# SCH_A320_MCDU_SMD_2023-03-02.net
KiCad netlist of a schematic drawn in EasyEDA
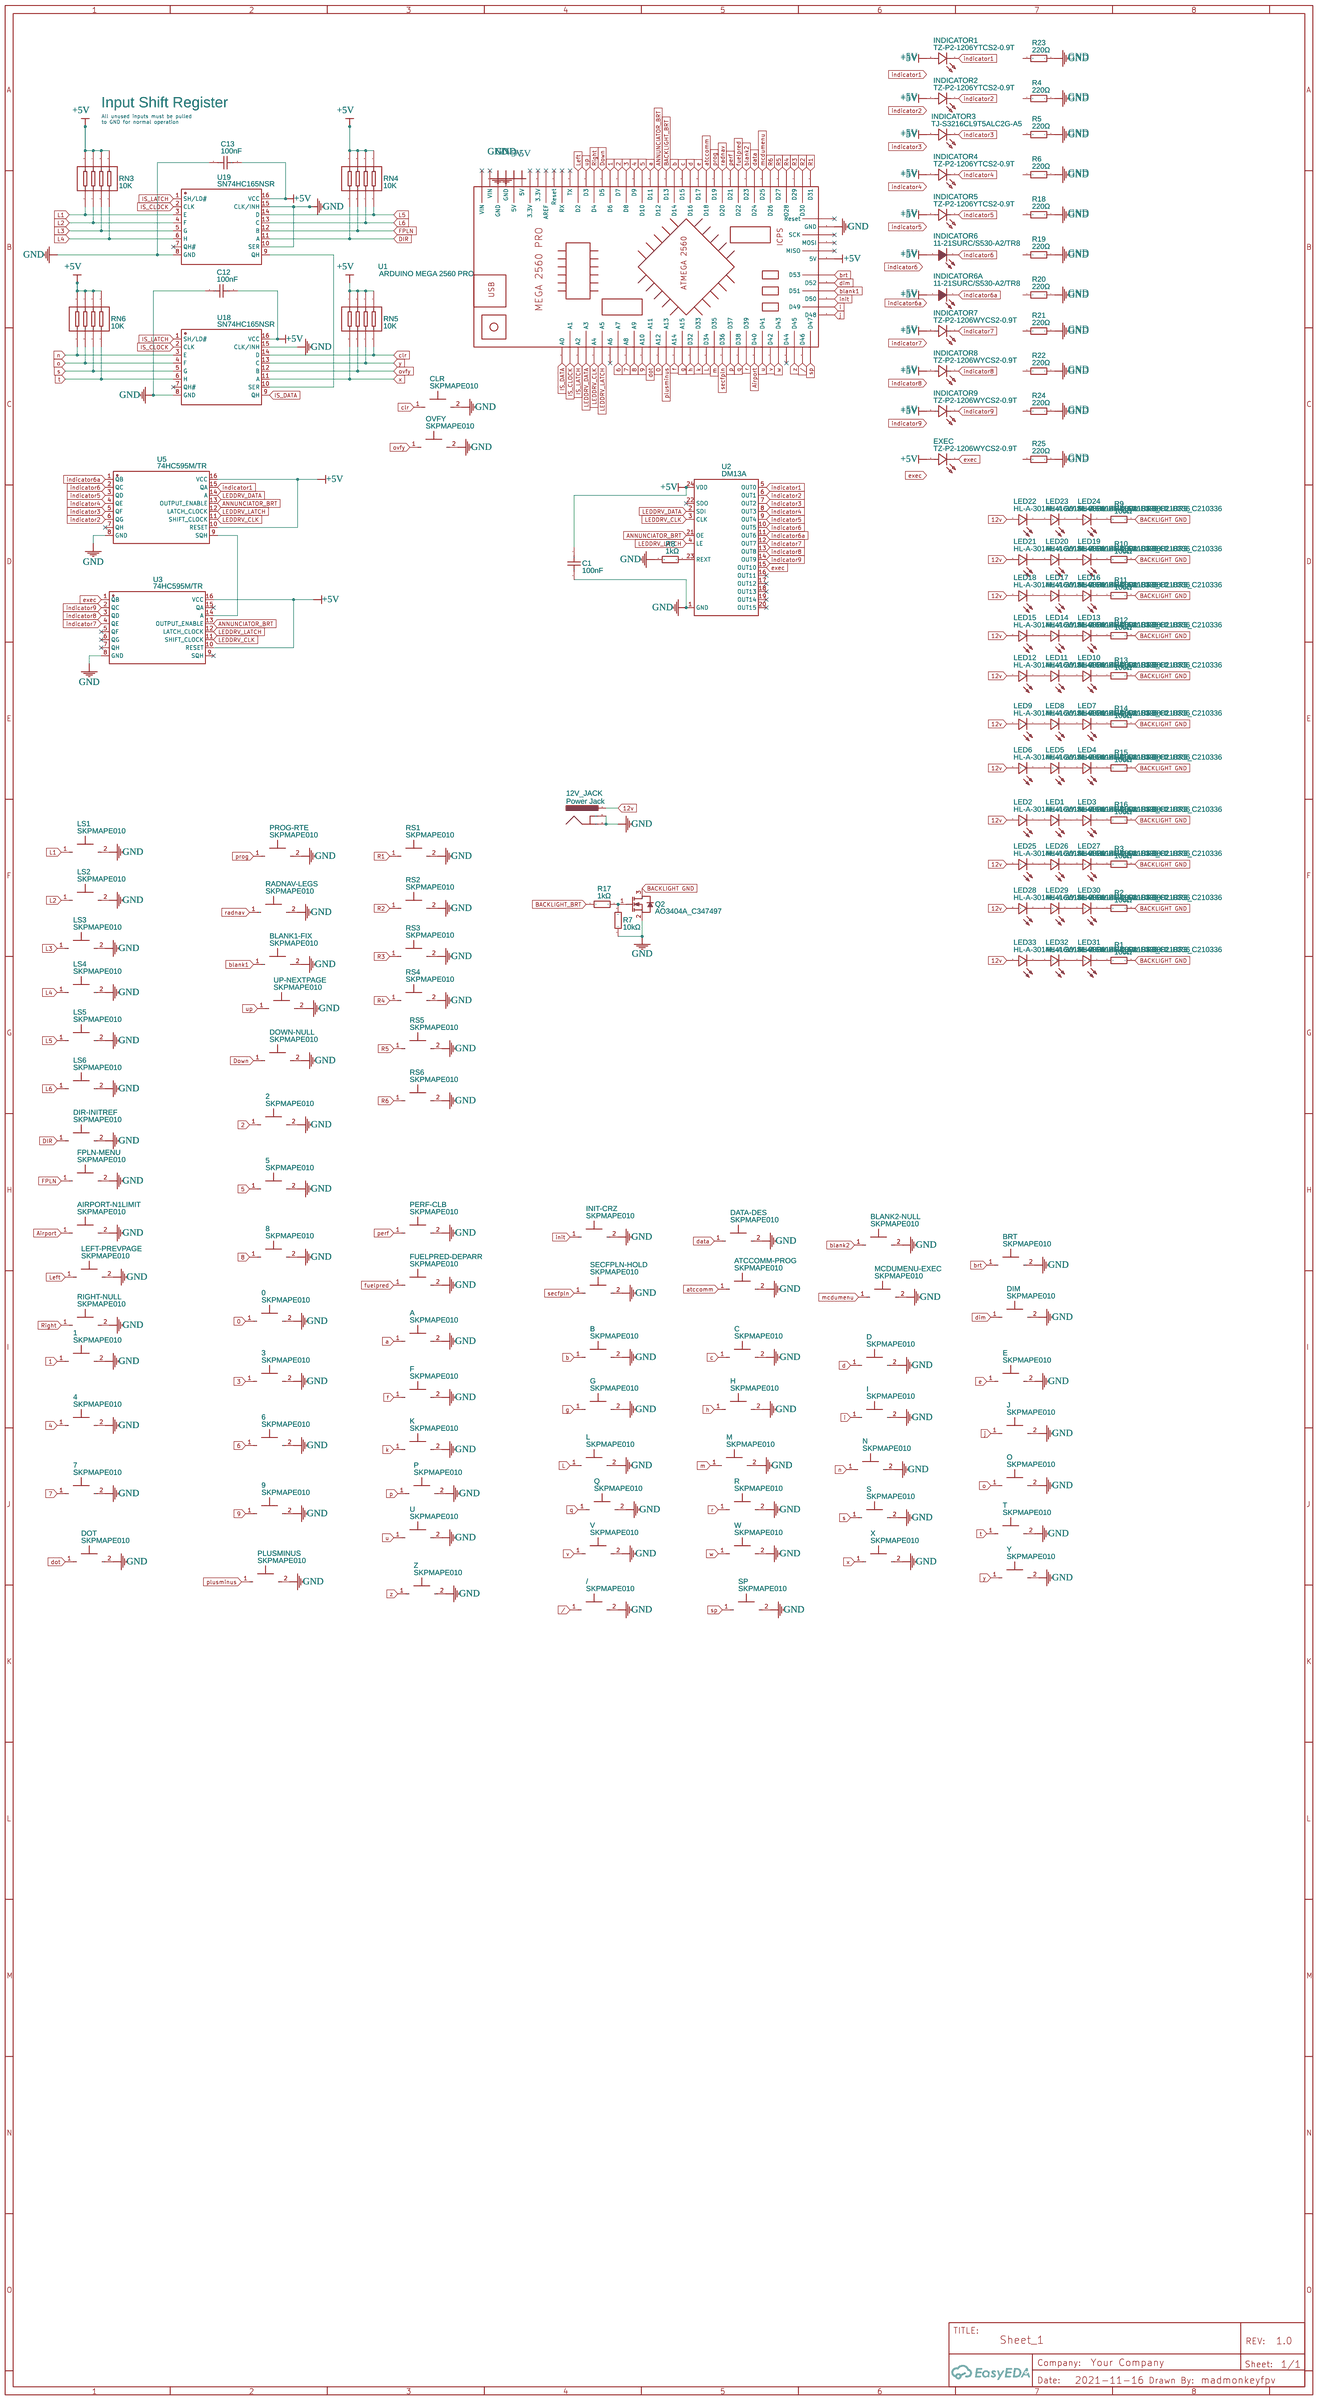
[diagram p0: schematic sheet]

(export (version "E")
  (design (tool "Eeschema 10.0.6"))
  (components
    (comp (ref "/")
      (value "SKPMAPE010")
      (fields (field (name "BOM_Supplier Part") "C110292"))
      (libsource (lib "") (part "SKPMAPE010_19"))
    )
    (comp (ref "0")
      (value "SKPMAPE010")
      (fields (field (name "BOM_Supplier Part") "C110292"))
      (libsource (lib "") (part "SKPMAPE010_6"))
    )
    (comp (ref "1")
      (value "SKPMAPE010")
      (fields (field (name "BOM_Supplier Part") "C110292"))
      (libsource (lib "") (part "SKPMAPE010_6"))
    )
    (comp (ref "2")
      (value "SKPMAPE010")
      (fields (field (name "BOM_Supplier Part") "C110292"))
      (libsource (lib "") (part "SKPMAPE010_6"))
    )
    (comp (ref "3")
      (value "SKPMAPE010")
      (fields (field (name "BOM_Supplier Part") "C110292"))
      (libsource (lib "") (part "SKPMAPE010_6"))
    )
    (comp (ref "4")
      (value "SKPMAPE010")
      (fields (field (name "BOM_Supplier Part") "C110292"))
      (libsource (lib "") (part "SKPMAPE010_6"))
    )
    (comp (ref "5")
      (value "SKPMAPE010")
      (fields (field (name "BOM_Supplier Part") "C110292"))
      (libsource (lib "") (part "SKPMAPE010_6"))
    )
    (comp (ref "6")
      (value "SKPMAPE010")
      (fields (field (name "BOM_Supplier Part") "C110292"))
      (libsource (lib "") (part "SKPMAPE010_6"))
    )
    (comp (ref "7")
      (value "SKPMAPE010")
      (fields (field (name "BOM_Supplier Part") "C110292"))
      (libsource (lib "") (part "SKPMAPE010_6"))
    )
    (comp (ref "8")
      (value "SKPMAPE010")
      (fields (field (name "BOM_Supplier Part") "C110292"))
      (libsource (lib "") (part "SKPMAPE010_6"))
    )
    (comp (ref "9")
      (value "SKPMAPE010")
      (fields (field (name "BOM_Supplier Part") "C110292"))
      (libsource (lib "") (part "SKPMAPE010_6"))
    )
    (comp (ref "12V_JACK")
      (value "Power Jack")
      (fields (field (name "BOM_Supplier Part") "A-4118"))
      (libsource (lib "") (part "POWER_JACK"))
    )
    (comp (ref "A")
      (value "SKPMAPE010")
      (fields (field (name "BOM_Supplier Part") "C110292"))
      (libsource (lib "") (part "SKPMAPE010_34"))
    )
    (comp (ref "AIRPORT-N1LIMIT")
      (value "SKPMAPE010")
      (fields (field (name "BOM_Supplier Part") "C110292"))
      (libsource (lib "") (part "SKPMAPE010_46"))
    )
    (comp (ref "ATCCOMM-PROG")
      (value "SKPMAPE010")
      (fields (field (name "BOM_Supplier Part") "C110292"))
      (libsource (lib "") (part "SKPMAPE010_37"))
    )
    (comp (ref "B")
      (value "SKPMAPE010")
      (fields (field (name "BOM_Supplier Part") "C110292"))
      (libsource (lib "") (part "SKPMAPE010_43"))
    )
    (comp (ref "BLANK1-FIX")
      (value "SKPMAPE010")
      (fields (field (name "BOM_Supplier Part") "C110292"))
      (libsource (lib "") (part "SKPMAPE010_17"))
    )
    (comp (ref "BLANK2-NULL")
      (value "SKPMAPE010")
      (fields (field (name "BOM_Supplier Part") "C110292"))
      (libsource (lib "") (part "SKPMAPE010_31"))
    )
    (comp (ref "BRT")
      (value "SKPMAPE010")
      (fields (field (name "BOM_Supplier Part") "C110292"))
      (libsource (lib "") (part "SKPMAPE010_32"))
    )
    (comp (ref "C")
      (value "SKPMAPE010")
      (fields (field (name "BOM_Supplier Part") "C110292"))
      (libsource (lib "") (part "SKPMAPE010_50"))
    )
    (comp (ref "C1")
      (value "100nF")
      (fields
        (field (name "BOM_Manufacturer Part") "CC0603KRX7R9BB104")
        (field (name "BOM_Supplier Part") "C14663")
      )
      (libsource (lib "") (part "CC0603KRX7R9BB104_1"))
    )
    (comp (ref "C12")
      (value "100nF")
      (fields
        (field (name "BOM_Manufacturer Part") "CC0603KRX7R9BB104")
        (field (name "BOM_Supplier Part") "C14663")
      )
      (libsource (lib "") (part "CC0603KRX7R9BB104"))
    )
    (comp (ref "C13")
      (value "100nF")
      (fields
        (field (name "BOM_Manufacturer Part") "CC0603KRX7R9BB104")
        (field (name "BOM_Supplier Part") "C14663")
      )
      (libsource (lib "") (part "CC0603KRX7R9BB104"))
    )
    (comp (ref "CLR")
      (value "SKPMAPE010")
      (fields (field (name "BOM_Supplier Part") "C110292"))
      (libsource (lib "") (part "SKPMAPE010_7"))
    )
    (comp (ref "D")
      (value "SKPMAPE010")
      (fields (field (name "BOM_Supplier Part") "C110292"))
      (libsource (lib "") (part "SKPMAPE010_54"))
    )
    (comp (ref "DATA-DES")
      (value "SKPMAPE010")
      (fields (field (name "BOM_Supplier Part") "C110292"))
      (libsource (lib "") (part "SKPMAPE010_28"))
    )
    (comp (ref "DIM")
      (value "SKPMAPE010")
      (fields (field (name "BOM_Supplier Part") "C110292"))
      (libsource (lib "") (part "SKPMAPE010_26"))
    )
    (comp (ref "DIR-INITREF")
      (value "SKPMAPE010")
      (fields (field (name "BOM_Supplier Part") "C110292"))
      (libsource (lib "") (part "SKPMAPE010_2"))
    )
    (comp (ref "DOT")
      (value "SKPMAPE010")
      (fields (field (name "BOM_Supplier Part") "C110292"))
      (libsource (lib "") (part "SKPMAPE010_20"))
    )
    (comp (ref "DOWN-NULL")
      (value "SKPMAPE010")
      (fields (field (name "BOM_Supplier Part") "C110292"))
      (libsource (lib "") (part "SKPMAPE010_33"))
    )
    (comp (ref "E")
      (value "SKPMAPE010")
      (fields (field (name "BOM_Supplier Part") "C110292"))
      (libsource (lib "") (part "SKPMAPE010_52"))
    )
    (comp (ref "EXEC")
      (value "TZ-P2-1206WYCS2-0.9T")
      (fields (field (name "BOM_Supplier Part") "C779809"))
      (libsource (lib "") (part "TZ-P2-1206WYCS2-0.9T_1"))
    )
    (comp (ref "F")
      (value "SKPMAPE010")
      (fields (field (name "BOM_Supplier Part") "C110292"))
      (libsource (lib "") (part "SKPMAPE010_45"))
    )
    (comp (ref "FPLN-MENU")
      (value "SKPMAPE010")
      (fields (field (name "BOM_Supplier Part") "C110292"))
      (libsource (lib "") (part "SKPMAPE010_48"))
    )
    (comp (ref "FUELPRED-DEPARR")
      (value "SKPMAPE010")
      (fields (field (name "BOM_Supplier Part") "C110292"))
      (libsource (lib "") (part "SKPMAPE010_18"))
    )
    (comp (ref "G")
      (value "SKPMAPE010")
      (fields (field (name "BOM_Supplier Part") "C110292"))
      (libsource (lib "") (part "SKPMAPE010_27"))
    )
    (comp (ref "H")
      (value "SKPMAPE010")
      (fields (field (name "BOM_Supplier Part") "C110292"))
      (libsource (lib "") (part "SKPMAPE010_5"))
    )
    (comp (ref "I")
      (value "SKPMAPE010")
      (fields (field (name "BOM_Supplier Part") "C110292"))
      (libsource (lib "") (part "SKPMAPE010_53"))
    )
    (comp (ref "INDICATOR1")
      (value "TZ-P2-1206YTCS2-0.9T")
      (fields (field (name "BOM_Supplier Part") "C779811"))
      (libsource (lib "") (part "TZ-P2-1206YTCS2-0.9T"))
    )
    (comp (ref "INDICATOR2")
      (value "TZ-P2-1206YTCS2-0.9T")
      (fields (field (name "BOM_Supplier Part") "C779811"))
      (libsource (lib "") (part "TZ-P2-1206YTCS2-0.9T"))
    )
    (comp (ref "INDICATOR3")
      (value "TJ-S3216CL9T5ALC2G-A5")
      (fields (field (name "BOM_Supplier Part") "C917196"))
      (libsource (lib "") (part "TJ-S3216CL9T5ALC2G-A5"))
    )
    (comp (ref "INDICATOR4")
      (value "TZ-P2-1206YTCS2-0.9T")
      (fields (field (name "BOM_Supplier Part") "C779811"))
      (libsource (lib "") (part "TZ-P2-1206YTCS2-0.9T"))
    )
    (comp (ref "INDICATOR5")
      (value "TZ-P2-1206YTCS2-0.9T")
      (fields (field (name "BOM_Supplier Part") "C779811"))
      (libsource (lib "") (part "TZ-P2-1206YTCS2-0.9T"))
    )
    (comp (ref "INDICATOR6")
      (value "11-21SURC/S530-A2/TR8")
      (fields (field (name "BOM_Supplier Part") "C264315"))
      (libsource (lib "") (part "11-21SURC/S530-A2/TR8"))
    )
    (comp (ref "INDICATOR6A")
      (value "11-21SURC/S530-A2/TR8")
      (fields (field (name "BOM_Supplier Part") "C264315"))
      (libsource (lib "") (part "11-21SURC/S530-A2/TR8_1"))
    )
    (comp (ref "INDICATOR7")
      (value "TZ-P2-1206WYCS2-0.9T")
      (fields (field (name "BOM_Supplier Part") "C779809"))
      (libsource (lib "") (part "TZ-P2-1206WYCS2-0.9T"))
    )
    (comp (ref "INDICATOR8")
      (value "TZ-P2-1206WYCS2-0.9T")
      (fields (field (name "BOM_Supplier Part") "C779809"))
      (libsource (lib "") (part "TZ-P2-1206WYCS2-0.9T"))
    )
    (comp (ref "INDICATOR9")
      (value "TZ-P2-1206WYCS2-0.9T")
      (fields (field (name "BOM_Supplier Part") "C779809"))
      (libsource (lib "") (part "TZ-P2-1206WYCS2-0.9T"))
    )
    (comp (ref "INIT-CRZ")
      (value "SKPMAPE010")
      (fields (field (name "BOM_Supplier Part") "C110292"))
      (libsource (lib "") (part "SKPMAPE010"))
    )
    (comp (ref "J")
      (value "SKPMAPE010")
      (fields (field (name "BOM_Supplier Part") "C110292"))
      (libsource (lib "") (part "SKPMAPE010_3"))
    )
    (comp (ref "K")
      (value "SKPMAPE010")
      (fields (field (name "BOM_Supplier Part") "C110292"))
      (libsource (lib "") (part "SKPMAPE010_9"))
    )
    (comp (ref "L")
      (value "SKPMAPE010")
      (fields (field (name "BOM_Supplier Part") "C110292"))
      (libsource (lib "") (part "SKPMAPE010_8"))
    )
    (comp (ref "LED1")
      (value "HL-A-3014H416W-S1-08HL-HR3_C210336")
      (fields (field (name "BOM_Supplier Part") "C210336"))
      (libsource (lib "") (part "HL-A-3014H416W-S1-08HL-HR3_C210336"))
    )
    (comp (ref "LED2")
      (value "HL-A-3014H416W-S1-08HL-HR3_C210336")
      (fields (field (name "BOM_Supplier Part") "C210336"))
      (libsource (lib "") (part "HL-A-3014H416W-S1-08HL-HR3_C210336"))
    )
    (comp (ref "LED3")
      (value "HL-A-3014H416W-S1-08HL-HR3_C210336")
      (fields (field (name "BOM_Supplier Part") "C210336"))
      (libsource (lib "") (part "HL-A-3014H416W-S1-08HL-HR3_C210336"))
    )
    (comp (ref "LED4")
      (value "HL-A-3014H416W-S1-08HL-HR3_C210336")
      (fields (field (name "BOM_Supplier Part") "C210336"))
      (libsource (lib "") (part "HL-A-3014H416W-S1-08HL-HR3_C210336"))
    )
    (comp (ref "LED5")
      (value "HL-A-3014H416W-S1-08HL-HR3_C210336")
      (fields (field (name "BOM_Supplier Part") "C210336"))
      (libsource (lib "") (part "HL-A-3014H416W-S1-08HL-HR3_C210336"))
    )
    (comp (ref "LED6")
      (value "HL-A-3014H416W-S1-08HL-HR3_C210336")
      (fields (field (name "BOM_Supplier Part") "C210336"))
      (libsource (lib "") (part "HL-A-3014H416W-S1-08HL-HR3_C210336"))
    )
    (comp (ref "LED7")
      (value "HL-A-3014H416W-S1-08HL-HR3_C210336")
      (fields (field (name "BOM_Supplier Part") "C210336"))
      (libsource (lib "") (part "HL-A-3014H416W-S1-08HL-HR3_C210336"))
    )
    (comp (ref "LED8")
      (value "HL-A-3014H416W-S1-08HL-HR3_C210336")
      (fields (field (name "BOM_Supplier Part") "C210336"))
      (libsource (lib "") (part "HL-A-3014H416W-S1-08HL-HR3_C210336"))
    )
    (comp (ref "LED9")
      (value "HL-A-3014H416W-S1-08HL-HR3_C210336")
      (fields (field (name "BOM_Supplier Part") "C210336"))
      (libsource (lib "") (part "HL-A-3014H416W-S1-08HL-HR3_C210336"))
    )
    (comp (ref "LED10")
      (value "HL-A-3014H416W-S1-08HL-HR3_C210336")
      (fields (field (name "BOM_Supplier Part") "C210336"))
      (libsource (lib "") (part "HL-A-3014H416W-S1-08HL-HR3_C210336"))
    )
    (comp (ref "LED11")
      (value "HL-A-3014H416W-S1-08HL-HR3_C210336")
      (fields (field (name "BOM_Supplier Part") "C210336"))
      (libsource (lib "") (part "HL-A-3014H416W-S1-08HL-HR3_C210336"))
    )
    (comp (ref "LED12")
      (value "HL-A-3014H416W-S1-08HL-HR3_C210336")
      (fields (field (name "BOM_Supplier Part") "C210336"))
      (libsource (lib "") (part "HL-A-3014H416W-S1-08HL-HR3_C210336"))
    )
    (comp (ref "LED13")
      (value "HL-A-3014H416W-S1-08HL-HR3_C210336")
      (fields (field (name "BOM_Supplier Part") "C210336"))
      (libsource (lib "") (part "HL-A-3014H416W-S1-08HL-HR3_C210336"))
    )
    (comp (ref "LED14")
      (value "HL-A-3014H416W-S1-08HL-HR3_C210336")
      (fields (field (name "BOM_Supplier Part") "C210336"))
      (libsource (lib "") (part "HL-A-3014H416W-S1-08HL-HR3_C210336"))
    )
    (comp (ref "LED15")
      (value "HL-A-3014H416W-S1-08HL-HR3_C210336")
      (fields (field (name "BOM_Supplier Part") "C210336"))
      (libsource (lib "") (part "HL-A-3014H416W-S1-08HL-HR3_C210336"))
    )
    (comp (ref "LED16")
      (value "HL-A-3014H416W-S1-08HL-HR3_C210336")
      (fields (field (name "BOM_Supplier Part") "C210336"))
      (libsource (lib "") (part "HL-A-3014H416W-S1-08HL-HR3_C210336"))
    )
    (comp (ref "LED17")
      (value "HL-A-3014H416W-S1-08HL-HR3_C210336")
      (fields (field (name "BOM_Supplier Part") "C210336"))
      (libsource (lib "") (part "HL-A-3014H416W-S1-08HL-HR3_C210336"))
    )
    (comp (ref "LED18")
      (value "HL-A-3014H416W-S1-08HL-HR3_C210336")
      (fields (field (name "BOM_Supplier Part") "C210336"))
      (libsource (lib "") (part "HL-A-3014H416W-S1-08HL-HR3_C210336"))
    )
    (comp (ref "LED19")
      (value "HL-A-3014H416W-S1-08HL-HR3_C210336")
      (fields (field (name "BOM_Supplier Part") "C210336"))
      (libsource (lib "") (part "HL-A-3014H416W-S1-08HL-HR3_C210336"))
    )
    (comp (ref "LED20")
      (value "HL-A-3014H416W-S1-08HL-HR3_C210336")
      (fields (field (name "BOM_Supplier Part") "C210336"))
      (libsource (lib "") (part "HL-A-3014H416W-S1-08HL-HR3_C210336"))
    )
    (comp (ref "LED21")
      (value "HL-A-3014H416W-S1-08HL-HR3_C210336")
      (fields (field (name "BOM_Supplier Part") "C210336"))
      (libsource (lib "") (part "HL-A-3014H416W-S1-08HL-HR3_C210336"))
    )
    (comp (ref "LED22")
      (value "HL-A-3014H416W-S1-08HL-HR3_C210336")
      (fields (field (name "BOM_Supplier Part") "C210336"))
      (libsource (lib "") (part "HL-A-3014H416W-S1-08HL-HR3_C210336"))
    )
    (comp (ref "LED23")
      (value "HL-A-3014H416W-S1-08HL-HR3_C210336")
      (fields (field (name "BOM_Supplier Part") "C210336"))
      (libsource (lib "") (part "HL-A-3014H416W-S1-08HL-HR3_C210336"))
    )
    (comp (ref "LED24")
      (value "HL-A-3014H416W-S1-08HL-HR3_C210336")
      (fields (field (name "BOM_Supplier Part") "C210336"))
      (libsource (lib "") (part "HL-A-3014H416W-S1-08HL-HR3_C210336"))
    )
    (comp (ref "LED25")
      (value "HL-A-3014H416W-S1-08HL-HR3_C210336")
      (fields (field (name "BOM_Supplier Part") "C210336"))
      (libsource (lib "") (part "HL-A-3014H416W-S1-08HL-HR3_C210336"))
    )
    (comp (ref "LED26")
      (value "HL-A-3014H416W-S1-08HL-HR3_C210336")
      (fields (field (name "BOM_Supplier Part") "C210336"))
      (libsource (lib "") (part "HL-A-3014H416W-S1-08HL-HR3_C210336"))
    )
    (comp (ref "LED27")
      (value "HL-A-3014H416W-S1-08HL-HR3_C210336")
      (fields (field (name "BOM_Supplier Part") "C210336"))
      (libsource (lib "") (part "HL-A-3014H416W-S1-08HL-HR3_C210336"))
    )
    (comp (ref "LED28")
      (value "HL-A-3014H416W-S1-08HL-HR3_C210336")
      (fields (field (name "BOM_Supplier Part") "C210336"))
      (libsource (lib "") (part "HL-A-3014H416W-S1-08HL-HR3_C210336"))
    )
    (comp (ref "LED29")
      (value "HL-A-3014H416W-S1-08HL-HR3_C210336")
      (fields (field (name "BOM_Supplier Part") "C210336"))
      (libsource (lib "") (part "HL-A-3014H416W-S1-08HL-HR3_C210336"))
    )
    (comp (ref "LED30")
      (value "HL-A-3014H416W-S1-08HL-HR3_C210336")
      (fields (field (name "BOM_Supplier Part") "C210336"))
      (libsource (lib "") (part "HL-A-3014H416W-S1-08HL-HR3_C210336"))
    )
    (comp (ref "LED31")
      (value "HL-A-3014H416W-S1-08HL-HR3_C210336")
      (fields (field (name "BOM_Supplier Part") "C210336"))
      (libsource (lib "") (part "HL-A-3014H416W-S1-08HL-HR3_C210336"))
    )
    (comp (ref "LED32")
      (value "HL-A-3014H416W-S1-08HL-HR3_C210336")
      (fields (field (name "BOM_Supplier Part") "C210336"))
      (libsource (lib "") (part "HL-A-3014H416W-S1-08HL-HR3_C210336"))
    )
    (comp (ref "LED33")
      (value "HL-A-3014H416W-S1-08HL-HR3_C210336")
      (fields (field (name "BOM_Supplier Part") "C210336"))
      (libsource (lib "") (part "HL-A-3014H416W-S1-08HL-HR3_C210336"))
    )
    (comp (ref "LEFT-PREVPAGE")
      (value "SKPMAPE010")
      (fields (field (name "BOM_Supplier Part") "C110292"))
      (libsource (lib "") (part "SKPMAPE010_14"))
    )
    (comp (ref "LS1")
      (value "SKPMAPE010")
      (fields (field (name "BOM_Supplier Part") "C110292"))
      (libsource (lib "") (part "SKPMAPE010_12"))
    )
    (comp (ref "LS2")
      (value "SKPMAPE010")
      (fields (field (name "BOM_Supplier Part") "C110292"))
      (libsource (lib "") (part "SKPMAPE010_12"))
    )
    (comp (ref "LS3")
      (value "SKPMAPE010")
      (fields (field (name "BOM_Supplier Part") "C110292"))
      (libsource (lib "") (part "SKPMAPE010_12"))
    )
    (comp (ref "LS4")
      (value "SKPMAPE010")
      (fields (field (name "BOM_Supplier Part") "C110292"))
      (libsource (lib "") (part "SKPMAPE010_12"))
    )
    (comp (ref "LS5")
      (value "SKPMAPE010")
      (fields (field (name "BOM_Supplier Part") "C110292"))
      (libsource (lib "") (part "SKPMAPE010_12"))
    )
    (comp (ref "LS6")
      (value "SKPMAPE010")
      (fields (field (name "BOM_Supplier Part") "C110292"))
      (libsource (lib "") (part "SKPMAPE010_12"))
    )
    (comp (ref "M")
      (value "SKPMAPE010")
      (fields (field (name "BOM_Supplier Part") "C110292"))
      (libsource (lib "") (part "SKPMAPE010_41"))
    )
    (comp (ref "MCDUMENU-EXEC")
      (value "SKPMAPE010")
      (fields (field (name "BOM_Supplier Part") "C110292"))
      (libsource (lib "") (part "SKPMAPE010_24"))
    )
    (comp (ref "N")
      (value "SKPMAPE010")
      (fields (field (name "BOM_Supplier Part") "C110292"))
      (libsource (lib "") (part "SKPMAPE010_49"))
    )
    (comp (ref "O")
      (value "SKPMAPE010")
      (fields (field (name "BOM_Supplier Part") "C110292"))
      (libsource (lib "") (part "SKPMAPE010_1"))
    )
    (comp (ref "OVFY")
      (value "SKPMAPE010")
      (fields (field (name "BOM_Supplier Part") "C110292"))
      (libsource (lib "") (part "SKPMAPE010_4"))
    )
    (comp (ref "P")
      (value "SKPMAPE010")
      (fields (field (name "BOM_Supplier Part") "C110292"))
      (libsource (lib "") (part "SKPMAPE010_35"))
    )
    (comp (ref "PERF-CLB")
      (value "SKPMAPE010")
      (fields (field (name "BOM_Supplier Part") "C110292"))
      (libsource (lib "") (part "SKPMAPE010_44"))
    )
    (comp (ref "PLUSMINUS")
      (value "SKPMAPE010")
      (fields (field (name "BOM_Supplier Part") "C110292"))
      (libsource (lib "") (part "SKPMAPE010_21"))
    )
    (comp (ref "PROG-RTE")
      (value "SKPMAPE010")
      (fields (field (name "BOM_Supplier Part") "C110292"))
      (libsource (lib "") (part "SKPMAPE010_11"))
    )
    (comp (ref "Q")
      (value "SKPMAPE010")
      (fields (field (name "BOM_Supplier Part") "C110292"))
      (libsource (lib "") (part "SKPMAPE010_30"))
    )
    (comp (ref "Q2")
      (value "AO3404A_C347497")
      (fields (field (name "BOM_Manufacturer Part") "AO3404A") (field (name "BOM_Supplier Part") "C347497"))
      (libsource (lib "") (part "AO3404A_C347497"))
    )
    (comp (ref "R")
      (value "SKPMAPE010")
      (fields (field (name "BOM_Supplier Part") "C110292"))
      (libsource (lib "") (part "SKPMAPE010_29"))
    )
    (comp (ref "R1")
      (value "100Ω")
      (fields
        (field (name "BOM_Manufacturer Part") "1206W4F1000T5E")
        (field (name "BOM_Supplier Part") "C17901")
      )
      (libsource (lib "") (part "1206W4F1000T5E"))
    )
    (comp (ref "R2")
      (value "100Ω")
      (fields
        (field (name "BOM_Manufacturer Part") "1206W4F1000T5E")
        (field (name "BOM_Supplier Part") "C17901")
      )
      (libsource (lib "") (part "1206W4F1000T5E"))
    )
    (comp (ref "R3")
      (value "100Ω")
      (fields
        (field (name "BOM_Manufacturer Part") "1206W4F1000T5E")
        (field (name "BOM_Supplier Part") "C17901")
      )
      (libsource (lib "") (part "1206W4F1000T5E"))
    )
    (comp (ref "R4")
      (value "220Ω")
      (fields
        (field (name "BOM_Manufacturer Part") "0805W8F2200T5E")
        (field (name "BOM_Supplier Part") "C17557")
      )
      (libsource (lib "") (part "0805W8F2200T5E"))
    )
    (comp (ref "R5")
      (value "220Ω")
      (fields
        (field (name "BOM_Manufacturer Part") "0805W8F2200T5E")
        (field (name "BOM_Supplier Part") "C17557")
      )
      (libsource (lib "") (part "0805W8F2200T5E"))
    )
    (comp (ref "R6")
      (value "220Ω")
      (fields
        (field (name "BOM_Manufacturer Part") "0805W8F2200T5E")
        (field (name "BOM_Supplier Part") "C17557")
      )
      (libsource (lib "") (part "0805W8F2200T5E"))
    )
    (comp (ref "R7")
      (value "10kΩ")
      (fields
        (field (name "BOM_Manufacturer Part") "1206W4F1002T5E")
        (field (name "BOM_Supplier Part") "C17902")
      )
      (libsource (lib "") (part "1206W4F1002T5E"))
    )
    (comp (ref "R8")
      (value "1kΩ")
      (fields
        (field (name "BOM_Manufacturer Part") "1206W4F1001T5E")
        (field (name "BOM_Supplier Part") "C4410")
      )
      (libsource (lib "") (part "1206W4F1001T5E_1"))
    )
    (comp (ref "R9")
      (value "100Ω")
      (fields
        (field (name "BOM_Manufacturer Part") "1206W4F1000T5E")
        (field (name "BOM_Supplier Part") "C17901")
      )
      (libsource (lib "") (part "1206W4F1000T5E"))
    )
    (comp (ref "R10")
      (value "100Ω")
      (fields
        (field (name "BOM_Manufacturer Part") "1206W4F1000T5E")
        (field (name "BOM_Supplier Part") "C17901")
      )
      (libsource (lib "") (part "1206W4F1000T5E"))
    )
    (comp (ref "R11")
      (value "100Ω")
      (fields
        (field (name "BOM_Manufacturer Part") "1206W4F1000T5E")
        (field (name "BOM_Supplier Part") "C17901")
      )
      (libsource (lib "") (part "1206W4F1000T5E"))
    )
    (comp (ref "R12")
      (value "100Ω")
      (fields
        (field (name "BOM_Manufacturer Part") "1206W4F1000T5E")
        (field (name "BOM_Supplier Part") "C17901")
      )
      (libsource (lib "") (part "1206W4F1000T5E"))
    )
    (comp (ref "R13")
      (value "100Ω")
      (fields
        (field (name "BOM_Manufacturer Part") "1206W4F1000T5E")
        (field (name "BOM_Supplier Part") "C17901")
      )
      (libsource (lib "") (part "1206W4F1000T5E"))
    )
    (comp (ref "R14")
      (value "100Ω")
      (fields
        (field (name "BOM_Manufacturer Part") "1206W4F1000T5E")
        (field (name "BOM_Supplier Part") "C17901")
      )
      (libsource (lib "") (part "1206W4F1000T5E"))
    )
    (comp (ref "R15")
      (value "100Ω")
      (fields
        (field (name "BOM_Manufacturer Part") "1206W4F1000T5E")
        (field (name "BOM_Supplier Part") "C17901")
      )
      (libsource (lib "") (part "1206W4F1000T5E"))
    )
    (comp (ref "R16")
      (value "100Ω")
      (fields
        (field (name "BOM_Manufacturer Part") "1206W4F1000T5E")
        (field (name "BOM_Supplier Part") "C17901")
      )
      (libsource (lib "") (part "1206W4F1000T5E"))
    )
    (comp (ref "R17")
      (value "1kΩ")
      (fields
        (field (name "BOM_Manufacturer Part") "1206W4F1001T5E")
        (field (name "BOM_Supplier Part") "C4410")
      )
      (libsource (lib "") (part "1206W4F1001T5E"))
    )
    (comp (ref "R18")
      (value "220Ω")
      (fields
        (field (name "BOM_Manufacturer Part") "0805W8F2200T5E")
        (field (name "BOM_Supplier Part") "C17557")
      )
      (libsource (lib "") (part "0805W8F2200T5E"))
    )
    (comp (ref "R19")
      (value "220Ω")
      (fields
        (field (name "BOM_Manufacturer Part") "0805W8F2200T5E")
        (field (name "BOM_Supplier Part") "C17557")
      )
      (libsource (lib "") (part "0805W8F2200T5E"))
    )
    (comp (ref "R20")
      (value "220Ω")
      (fields
        (field (name "BOM_Manufacturer Part") "0805W8F2200T5E")
        (field (name "BOM_Supplier Part") "C17557")
      )
      (libsource (lib "") (part "0805W8F2200T5E"))
    )
    (comp (ref "R21")
      (value "220Ω")
      (fields
        (field (name "BOM_Manufacturer Part") "0805W8F2200T5E")
        (field (name "BOM_Supplier Part") "C17557")
      )
      (libsource (lib "") (part "0805W8F2200T5E"))
    )
    (comp (ref "R22")
      (value "220Ω")
      (fields
        (field (name "BOM_Manufacturer Part") "0805W8F2200T5E")
        (field (name "BOM_Supplier Part") "C17557")
      )
      (libsource (lib "") (part "0805W8F2200T5E"))
    )
    (comp (ref "R23")
      (value "220Ω")
      (fields
        (field (name "BOM_Manufacturer Part") "0805W8F2200T5E")
        (field (name "BOM_Supplier Part") "C17557")
      )
      (libsource (lib "") (part "0805W8F2200T5E"))
    )
    (comp (ref "R24")
      (value "220Ω")
      (fields
        (field (name "BOM_Manufacturer Part") "0805W8F2200T5E")
        (field (name "BOM_Supplier Part") "C17557")
      )
      (libsource (lib "") (part "0805W8F2200T5E"))
    )
    (comp (ref "R25")
      (value "220Ω")
      (fields
        (field (name "BOM_Manufacturer Part") "0805W8F2200T5E")
        (field (name "BOM_Supplier Part") "C17557")
      )
      (libsource (lib "") (part "0805W8F2200T5E"))
    )
    (comp (ref "RADNAV-LEGS")
      (value "SKPMAPE010")
      (fields (field (name "BOM_Supplier Part") "C110292"))
      (libsource (lib "") (part "SKPMAPE010_23"))
    )
    (comp (ref "RIGHT-NULL")
      (value "SKPMAPE010")
      (fields (field (name "BOM_Supplier Part") "C110292"))
      (libsource (lib "") (part "SKPMAPE010_47"))
    )
    (comp (ref "RN3")
      (value "10K")
      (fields
        (field (name "BOM_Manufacturer Part") "YC164-FR-0710KL")
        (field (name "BOM_Supplier Part") "C110924")
      )
      (libsource (lib "") (part "YC164-FR-0710KL"))
    )
    (comp (ref "RN4")
      (value "10K")
      (fields
        (field (name "BOM_Manufacturer Part") "YC164-FR-0710KL")
        (field (name "BOM_Supplier Part") "C110924")
      )
      (libsource (lib "") (part "YC164-FR-0710KL_1"))
    )
    (comp (ref "RN5")
      (value "10K")
      (fields
        (field (name "BOM_Manufacturer Part") "YC164-FR-0710KL")
        (field (name "BOM_Supplier Part") "C110924")
      )
      (libsource (lib "") (part "YC164-FR-0710KL_1"))
    )
    (comp (ref "RN6")
      (value "10K")
      (fields
        (field (name "BOM_Manufacturer Part") "YC164-FR-0710KL")
        (field (name "BOM_Supplier Part") "C110924")
      )
      (libsource (lib "") (part "YC164-FR-0710KL"))
    )
    (comp (ref "RS1")
      (value "SKPMAPE010")
      (fields (field (name "BOM_Supplier Part") "C110292"))
      (libsource (lib "") (part "SKPMAPE010_16"))
    )
    (comp (ref "RS2")
      (value "SKPMAPE010")
      (fields (field (name "BOM_Supplier Part") "C110292"))
      (libsource (lib "") (part "SKPMAPE010_16"))
    )
    (comp (ref "RS3")
      (value "SKPMAPE010")
      (fields (field (name "BOM_Supplier Part") "C110292"))
      (libsource (lib "") (part "SKPMAPE010_16"))
    )
    (comp (ref "RS4")
      (value "SKPMAPE010")
      (fields (field (name "BOM_Supplier Part") "C110292"))
      (libsource (lib "") (part "SKPMAPE010_16"))
    )
    (comp (ref "RS5")
      (value "SKPMAPE010")
      (fields (field (name "BOM_Supplier Part") "C110292"))
      (libsource (lib "") (part "SKPMAPE010_16"))
    )
    (comp (ref "RS6")
      (value "SKPMAPE010")
      (fields (field (name "BOM_Supplier Part") "C110292"))
      (libsource (lib "") (part "SKPMAPE010_16"))
    )
    (comp (ref "S")
      (value "SKPMAPE010")
      (fields (field (name "BOM_Supplier Part") "C110292"))
      (libsource (lib "") (part "SKPMAPE010_39"))
    )
    (comp (ref "SECFPLN-HOLD")
      (value "SKPMAPE010")
      (fields (field (name "BOM_Supplier Part") "C110292"))
      (libsource (lib "") (part "SKPMAPE010_13"))
    )
    (comp (ref "SP")
      (value "SKPMAPE010")
      (fields (field (name "BOM_Supplier Part") "C110292"))
      (libsource (lib "") (part "SKPMAPE010_22"))
    )
    (comp (ref "T")
      (value "SKPMAPE010")
      (fields (field (name "BOM_Supplier Part") "C110292"))
      (libsource (lib "") (part "SKPMAPE010_36"))
    )
    (comp (ref "U")
      (value "SKPMAPE010")
      (fields (field (name "BOM_Supplier Part") "C110292"))
      (libsource (lib "") (part "SKPMAPE010_25"))
    )
    (comp (ref "U1")
      (value "ARDUINO MEGA 2560 PRO")
      (fields (field (name "BOM_Manufacturer Part") "Arduino Mega 2560 Pro Mini"))
      (libsource (lib "") (part "ARDUINO MEGA 2560 PRO"))
    )
    (comp (ref "U2") (value "DM13A") (libsource (lib "") (part "DM13A")))
    (comp (ref "U3")
      (value "74HC595M/TR")
      (fields (field (name "BOM_Supplier Part") "C507176"))
      (libsource (lib "") (part "74HC595M/TR"))
    )
    (comp (ref "U5")
      (value "74HC595M/TR")
      (fields (field (name "BOM_Supplier Part") "C507176"))
      (libsource (lib "") (part "74HC595M/TR"))
    )
    (comp (ref "U18")
      (value "SN74HC165NSR")
      (fields (field (name "BOM_Supplier Part") "C129935"))
      (libsource (lib "") (part "SN74HC165NSR"))
    )
    (comp (ref "U19")
      (value "SN74HC165NSR")
      (fields (field (name "BOM_Supplier Part") "C129935"))
      (libsource (lib "") (part "SN74HC165NSR"))
    )
    (comp (ref "UP-NEXTPAGE")
      (value "SKPMAPE010")
      (fields (field (name "BOM_Supplier Part") "C110292"))
      (libsource (lib "") (part "SKPMAPE010_40"))
    )
    (comp (ref "V")
      (value "SKPMAPE010")
      (fields (field (name "BOM_Supplier Part") "C110292"))
      (libsource (lib "") (part "SKPMAPE010_10"))
    )
    (comp (ref "W")
      (value "SKPMAPE010")
      (fields (field (name "BOM_Supplier Part") "C110292"))
      (libsource (lib "") (part "SKPMAPE010_15"))
    )
    (comp (ref "X")
      (value "SKPMAPE010")
      (fields (field (name "BOM_Supplier Part") "C110292"))
      (libsource (lib "") (part "SKPMAPE010_42"))
    )
    (comp (ref "Y")
      (value "SKPMAPE010")
      (fields (field (name "BOM_Supplier Part") "C110292"))
      (libsource (lib "") (part "SKPMAPE010_51"))
    )
    (comp (ref "Z")
      (value "SKPMAPE010")
      (fields (field (name "BOM_Supplier Part") "C110292"))
      (libsource (lib "") (part "SKPMAPE010_38"))
    )
  )
  (nets
    (net (code "1") (name "+5V") (class "Default")
      (node (ref "C1") (pin "1") (pinfunction "1_1") (pintype "unspecified"))
      (node (ref "C12") (pin "2") (pinfunction "2_2") (pintype "unspecified"))
      (node (ref "C13") (pin "2") (pinfunction "2_2") (pintype "unspecified"))
      (node (ref "EXEC") (pin "2") (pinfunction "A_2") (pintype "unspecified"))
      (node (ref "INDICATOR1") (pin "2") (pinfunction "A_2") (pintype "unspecified"))
      (node (ref "INDICATOR2") (pin "2") (pinfunction "A_2") (pintype "unspecified"))
      (node (ref "INDICATOR3") (pin "2") (pinfunction "A_2") (pintype "unspecified"))
      (node (ref "INDICATOR4") (pin "2") (pinfunction "A_2") (pintype "unspecified"))
      (node (ref "INDICATOR5") (pin "2") (pinfunction "A_2") (pintype "unspecified"))
      (node (ref "INDICATOR6") (pin "1") (pinfunction "A_1") (pintype "unspecified"))
      (node (ref "INDICATOR6A") (pin "1") (pinfunction "A_1") (pintype "unspecified"))
      (node (ref "INDICATOR7") (pin "2") (pinfunction "A_2") (pintype "unspecified"))
      (node (ref "INDICATOR8") (pin "2") (pinfunction "A_2") (pintype "unspecified"))
      (node (ref "INDICATOR9") (pin "2") (pinfunction "A_2") (pintype "unspecified"))
      (node (ref "RN3") (pin "5") (pinfunction "5_5") (pintype "input"))
      (node (ref "RN3") (pin "6") (pinfunction "6_6") (pintype "input"))
      (node (ref "RN3") (pin "7") (pinfunction "7_7") (pintype "input"))
      (node (ref "RN3") (pin "8") (pinfunction "8_8") (pintype "input"))
      (node (ref "RN4") (pin "1") (pinfunction "1_1") (pintype "input"))
      (node (ref "RN4") (pin "2") (pinfunction "2_2") (pintype "input"))
      (node (ref "RN4") (pin "3") (pinfunction "3_3") (pintype "input"))
      (node (ref "RN4") (pin "4") (pinfunction "4_4") (pintype "input"))
      (node (ref "RN5") (pin "1") (pinfunction "1_1") (pintype "input"))
      (node (ref "RN5") (pin "2") (pinfunction "2_2") (pintype "input"))
      (node (ref "RN5") (pin "3") (pinfunction "3_3") (pintype "input"))
      (node (ref "RN5") (pin "4") (pinfunction "4_4") (pintype "input"))
      (node (ref "RN6") (pin "5") (pinfunction "5_5") (pintype "input"))
      (node (ref "RN6") (pin "6") (pinfunction "6_6") (pintype "input"))
      (node (ref "RN6") (pin "7") (pinfunction "7_7") (pintype "input"))
      (node (ref "RN6") (pin "8") (pinfunction "8_8") (pintype "input"))
      (node (ref "U1") (pin "39") (pinfunction "5V_39") (pintype "unspecified"))
      (node (ref "U1") (pin "81") (pinfunction "5V_81") (pintype "unspecified"))
      (node (ref "U1") (pin "82") (pinfunction "5V_82") (pintype "unspecified"))
      (node (ref "U18") (pin "16") (pinfunction "VCC_16") (pintype "unspecified"))
      (node (ref "U19") (pin "16") (pinfunction "VCC_16") (pintype "unspecified"))
      (node (ref "U2") (pin "24") (pinfunction "VDD_24") (pintype "unspecified"))
      (node (ref "U3") (pin "10") (pinfunction "RESET_10") (pintype "unspecified"))
      (node (ref "U3") (pin "16") (pinfunction "VCC_16") (pintype "unspecified"))
      (node (ref "U5") (pin "10") (pinfunction "RESET_10") (pintype "unspecified"))
      (node (ref "U5") (pin "16") (pinfunction "VCC_16") (pintype "unspecified"))
    )
    (net (code "2") (name "0") (class "Default")
      (node (ref "0") (pin "1") (pinfunction "1_1") (pintype "input"))
      (node (ref "U1") (pin "13") (pinfunction "A12_13") (pintype "unspecified"))
    )
    (net (code "3") (name "1") (class "Default")
      (node (ref "1") (pin "1") (pinfunction "1_1") (pintype "input"))
      (node (ref "U1") (pin "70") (pinfunction "D6_70") (pintype "unspecified"))
    )
    (net (code "4") (name "2") (class "Default")
      (node (ref "2") (pin "1") (pinfunction "1_1") (pintype "input"))
      (node (ref "U1") (pin "69") (pinfunction "D7_69") (pintype "unspecified"))
    )
    (net (code "5") (name "3") (class "Default")
      (node (ref "3") (pin "1") (pinfunction "1_1") (pintype "input"))
      (node (ref "U1") (pin "68") (pinfunction "D8_68") (pintype "unspecified"))
    )
    (net (code "6") (name "4") (class "Default")
      (node (ref "4") (pin "1") (pinfunction "1_1") (pintype "input"))
      (node (ref "U1") (pin "67") (pinfunction "D9_67") (pintype "unspecified"))
    )
    (net (code "7") (name "5") (class "Default")
      (node (ref "5") (pin "1") (pinfunction "1_1") (pintype "input"))
      (node (ref "U1") (pin "66") (pinfunction "D10_66") (pintype "unspecified"))
    )
    (net (code "8") (name "6") (class "Default")
      (node (ref "6") (pin "1") (pinfunction "1_1") (pintype "input"))
      (node (ref "U1") (pin "8") (pinfunction "A7_8") (pintype "unspecified"))
    )
    (net (code "9") (name "7") (class "Default")
      (node (ref "7") (pin "1") (pinfunction "1_1") (pintype "input"))
      (node (ref "U1") (pin "9") (pinfunction "A8_9") (pintype "unspecified"))
    )
    (net (code "10") (name "8") (class "Default")
      (node (ref "8") (pin "1") (pinfunction "1_1") (pintype "input"))
      (node (ref "U1") (pin "10") (pinfunction "A9_10") (pintype "unspecified"))
    )
    (net (code "11") (name "9") (class "Default")
      (node (ref "9") (pin "1") (pinfunction "1_1") (pintype "input"))
      (node (ref "U1") (pin "11") (pinfunction "A10_11") (pintype "unspecified"))
    )
    (net (code "12") (name "12v") (class "Default")
      (node (ref "12V_JACK") (pin "PWR") (pinfunction "PWR_PWR") (pintype "unspecified"))
      (node (ref "LED12") (pin "2") (pinfunction "2_2") (pintype "unspecified"))
      (node (ref "LED15") (pin "2") (pinfunction "2_2") (pintype "unspecified"))
      (node (ref "LED18") (pin "2") (pinfunction "2_2") (pintype "unspecified"))
      (node (ref "LED2") (pin "2") (pinfunction "2_2") (pintype "unspecified"))
      (node (ref "LED21") (pin "2") (pinfunction "2_2") (pintype "unspecified"))
      (node (ref "LED22") (pin "2") (pinfunction "2_2") (pintype "unspecified"))
      (node (ref "LED25") (pin "2") (pinfunction "2_2") (pintype "unspecified"))
      (node (ref "LED28") (pin "2") (pinfunction "2_2") (pintype "unspecified"))
      (node (ref "LED33") (pin "2") (pinfunction "2_2") (pintype "unspecified"))
      (node (ref "LED6") (pin "2") (pinfunction "2_2") (pintype "unspecified"))
      (node (ref "LED9") (pin "2") (pinfunction "2_2") (pintype "unspecified"))
    )
    (net (code "13") (name "ANNUNCIATOR_BRT") (class "Default")
      (node (ref "U1") (pin "64") (pinfunction "D12_64") (pintype "unspecified"))
      (node (ref "U2") (pin "21") (pinfunction "OE_21") (pintype "unspecified"))
      (node (ref "U3") (pin "13") (pinfunction "OUTPUT_ENABLE_13") (pintype "unspecified"))
      (node (ref "U5") (pin "13") (pinfunction "OUTPUT_ENABLE_13") (pintype "unspecified"))
    )
    (net (code "14") (name "Airport") (class "Default")
      (node (ref "AIRPORT-N1LIMIT") (pin "1") (pinfunction "1_1") (pintype "input"))
      (node (ref "U1") (pin "25") (pinfunction "D40_25") (pintype "unspecified"))
    )
    (net (code "15") (name "BACKLIGHT GND") (class "Default")
      (node (ref "Q2") (pin "3") (pinfunction "D_3") (pintype "unspecified"))
      (node (ref "R1") (pin "2") (pinfunction "2_2") (pintype "input"))
      (node (ref "R10") (pin "2") (pinfunction "2_2") (pintype "input"))
      (node (ref "R11") (pin "2") (pinfunction "2_2") (pintype "input"))
      (node (ref "R12") (pin "2") (pinfunction "2_2") (pintype "input"))
      (node (ref "R13") (pin "2") (pinfunction "2_2") (pintype "input"))
      (node (ref "R14") (pin "2") (pinfunction "2_2") (pintype "input"))
      (node (ref "R15") (pin "2") (pinfunction "2_2") (pintype "input"))
      (node (ref "R16") (pin "2") (pinfunction "2_2") (pintype "input"))
      (node (ref "R2") (pin "2") (pinfunction "2_2") (pintype "input"))
      (node (ref "R3") (pin "2") (pinfunction "2_2") (pintype "input"))
      (node (ref "R9") (pin "2") (pinfunction "2_2") (pintype "input"))
    )
    (net (code "16") (name "BACKLIGHT_BRT") (class "Default")
      (node (ref "R17") (pin "1") (pinfunction "1_1") (pintype "input"))
      (node (ref "U1") (pin "63") (pinfunction "D13_63") (pintype "unspecified"))
    )
    (net (code "17") (name "DIR") (class "Default")
      (node (ref "DIR-INITREF") (pin "1") (pinfunction "1_1") (pintype "input"))
      (node (ref "RN4") (pin "5") (pinfunction "5_5") (pintype "input"))
      (node (ref "U19") (pin "11") (pinfunction "A_11") (pintype "unspecified"))
    )
    (net (code "18") (name "Down") (class "Default")
      (node (ref "DOWN-NULL") (pin "1") (pinfunction "1_1") (pintype "input"))
      (node (ref "U1") (pin "71") (pinfunction "D5_71") (pintype "unspecified"))
    )
    (net (code "19") (name "FPLN") (class "Default")
      (node (ref "FPLN-MENU") (pin "1") (pinfunction "1_1") (pintype "input"))
      (node (ref "RN4") (pin "6") (pinfunction "6_6") (pintype "input"))
      (node (ref "U19") (pin "12") (pinfunction "B_12") (pintype "unspecified"))
    )
    (net (code "20") (name "GND") (class "Default")
      (node (ref "/") (pin "2") (pinfunction "2_2") (pintype "input"))
      (node (ref "0") (pin "2") (pinfunction "2_2") (pintype "input"))
      (node (ref "1") (pin "2") (pinfunction "2_2") (pintype "input"))
      (node (ref "12V_JACK") (pin "GND") (pinfunction "GND_GND") (pintype "unspecified"))
      (node (ref "12V_JACK") (pin "GNDBREAK") (pinfunction "GNDBREAK_GNDBREAK") (pintype "unspecified"))
      (node (ref "2") (pin "2") (pinfunction "2_2") (pintype "input"))
      (node (ref "3") (pin "2") (pinfunction "2_2") (pintype "input"))
      (node (ref "4") (pin "2") (pinfunction "2_2") (pintype "input"))
      (node (ref "5") (pin "2") (pinfunction "2_2") (pintype "input"))
      (node (ref "6") (pin "2") (pinfunction "2_2") (pintype "input"))
      (node (ref "7") (pin "2") (pinfunction "2_2") (pintype "input"))
      (node (ref "8") (pin "2") (pinfunction "2_2") (pintype "input"))
      (node (ref "9") (pin "2") (pinfunction "2_2") (pintype "input"))
      (node (ref "A") (pin "2") (pinfunction "2_2") (pintype "input"))
      (node (ref "AIRPORT-N1LIMIT") (pin "2") (pinfunction "2_2") (pintype "input"))
      (node (ref "ATCCOMM-PROG") (pin "2") (pinfunction "2_2") (pintype "input"))
      (node (ref "B") (pin "2") (pinfunction "2_2") (pintype "input"))
      (node (ref "BLANK1-FIX") (pin "2") (pinfunction "2_2") (pintype "input"))
      (node (ref "BLANK2-NULL") (pin "2") (pinfunction "2_2") (pintype "input"))
      (node (ref "BRT") (pin "2") (pinfunction "2_2") (pintype "input"))
      (node (ref "C") (pin "2") (pinfunction "2_2") (pintype "input"))
      (node (ref "C1") (pin "2") (pinfunction "2_2") (pintype "unspecified"))
      (node (ref "C12") (pin "1") (pinfunction "1_1") (pintype "unspecified"))
      (node (ref "C13") (pin "1") (pinfunction "1_1") (pintype "unspecified"))
      (node (ref "CLR") (pin "2") (pinfunction "2_2") (pintype "input"))
      (node (ref "D") (pin "2") (pinfunction "2_2") (pintype "input"))
      (node (ref "DATA-DES") (pin "2") (pinfunction "2_2") (pintype "input"))
      (node (ref "DIM") (pin "2") (pinfunction "2_2") (pintype "input"))
      (node (ref "DIR-INITREF") (pin "2") (pinfunction "2_2") (pintype "input"))
      (node (ref "DOT") (pin "2") (pinfunction "2_2") (pintype "input"))
      (node (ref "DOWN-NULL") (pin "2") (pinfunction "2_2") (pintype "input"))
      (node (ref "E") (pin "2") (pinfunction "2_2") (pintype "input"))
      (node (ref "F") (pin "2") (pinfunction "2_2") (pintype "input"))
      (node (ref "FPLN-MENU") (pin "2") (pinfunction "2_2") (pintype "input"))
      (node (ref "FUELPRED-DEPARR") (pin "2") (pinfunction "2_2") (pintype "input"))
      (node (ref "G") (pin "2") (pinfunction "2_2") (pintype "input"))
      (node (ref "H") (pin "2") (pinfunction "2_2") (pintype "input"))
      (node (ref "I") (pin "2") (pinfunction "2_2") (pintype "input"))
      (node (ref "INIT-CRZ") (pin "2") (pinfunction "2_2") (pintype "input"))
      (node (ref "J") (pin "2") (pinfunction "2_2") (pintype "input"))
      (node (ref "K") (pin "2") (pinfunction "2_2") (pintype "input"))
      (node (ref "L") (pin "2") (pinfunction "2_2") (pintype "input"))
      (node (ref "LEFT-PREVPAGE") (pin "2") (pinfunction "2_2") (pintype "input"))
      (node (ref "LS1") (pin "2") (pinfunction "2_2") (pintype "input"))
      (node (ref "LS2") (pin "2") (pinfunction "2_2") (pintype "input"))
      (node (ref "LS3") (pin "2") (pinfunction "2_2") (pintype "input"))
      (node (ref "LS4") (pin "2") (pinfunction "2_2") (pintype "input"))
      (node (ref "LS5") (pin "2") (pinfunction "2_2") (pintype "input"))
      (node (ref "LS6") (pin "2") (pinfunction "2_2") (pintype "input"))
      (node (ref "M") (pin "2") (pinfunction "2_2") (pintype "input"))
      (node (ref "MCDUMENU-EXEC") (pin "2") (pinfunction "2_2") (pintype "input"))
      (node (ref "N") (pin "2") (pinfunction "2_2") (pintype "input"))
      (node (ref "O") (pin "2") (pinfunction "2_2") (pintype "input"))
      (node (ref "OVFY") (pin "2") (pinfunction "2_2") (pintype "input"))
      (node (ref "P") (pin "2") (pinfunction "2_2") (pintype "input"))
      (node (ref "PERF-CLB") (pin "2") (pinfunction "2_2") (pintype "input"))
      (node (ref "PLUSMINUS") (pin "2") (pinfunction "2_2") (pintype "input"))
      (node (ref "PROG-RTE") (pin "2") (pinfunction "2_2") (pintype "input"))
      (node (ref "Q") (pin "2") (pinfunction "2_2") (pintype "input"))
      (node (ref "Q2") (pin "2") (pinfunction "S_2") (pintype "unspecified"))
      (node (ref "R") (pin "2") (pinfunction "2_2") (pintype "input"))
      (node (ref "R18") (pin "1") (pinfunction "1_1") (pintype "input"))
      (node (ref "R19") (pin "1") (pinfunction "1_1") (pintype "input"))
      (node (ref "R20") (pin "1") (pinfunction "1_1") (pintype "input"))
      (node (ref "R21") (pin "1") (pinfunction "1_1") (pintype "input"))
      (node (ref "R22") (pin "1") (pinfunction "1_1") (pintype "input"))
      (node (ref "R23") (pin "1") (pinfunction "1_1") (pintype "input"))
      (node (ref "R24") (pin "1") (pinfunction "1_1") (pintype "input"))
      (node (ref "R25") (pin "1") (pinfunction "1_1") (pintype "input"))
      (node (ref "R4") (pin "1") (pinfunction "1_1") (pintype "input"))
      (node (ref "R5") (pin "1") (pinfunction "1_1") (pintype "input"))
      (node (ref "R6") (pin "1") (pinfunction "1_1") (pintype "input"))
      (node (ref "R7") (pin "1") (pinfunction "1_1") (pintype "input"))
      (node (ref "R8") (pin "2") (pinfunction "2_2") (pintype "input"))
      (node (ref "RADNAV-LEGS") (pin "2") (pinfunction "2_2") (pintype "input"))
      (node (ref "RIGHT-NULL") (pin "2") (pinfunction "2_2") (pintype "input"))
      (node (ref "RS1") (pin "2") (pinfunction "2_2") (pintype "input"))
      (node (ref "RS2") (pin "2") (pinfunction "2_2") (pintype "input"))
      (node (ref "RS3") (pin "2") (pinfunction "2_2") (pintype "input"))
      (node (ref "RS4") (pin "2") (pinfunction "2_2") (pintype "input"))
      (node (ref "RS5") (pin "2") (pinfunction "2_2") (pintype "input"))
      (node (ref "RS6") (pin "2") (pinfunction "2_2") (pintype "input"))
      (node (ref "S") (pin "2") (pinfunction "2_2") (pintype "input"))
      (node (ref "SECFPLN-HOLD") (pin "2") (pinfunction "2_2") (pintype "input"))
      (node (ref "SP") (pin "2") (pinfunction "2_2") (pintype "input"))
      (node (ref "T") (pin "2") (pinfunction "2_2") (pintype "input"))
      (node (ref "U") (pin "2") (pinfunction "2_2") (pintype "input"))
      (node (ref "U1") (pin "43") (pinfunction "GND_43") (pintype "unspecified"))
      (node (ref "U1") (pin "83") (pinfunction "GND_83") (pintype "unspecified"))
      (node (ref "U1") (pin "84") (pinfunction "GND_84") (pintype "unspecified"))
      (node (ref "U18") (pin "15") (pinfunction "CLK/INH_15") (pintype "unspecified"))
      (node (ref "U18") (pin "8") (pinfunction "GND_8") (pintype "unspecified"))
      (node (ref "U19") (pin "10") (pinfunction "SER_10") (pintype "unspecified"))
      (node (ref "U19") (pin "15") (pinfunction "CLK/INH_15") (pintype "unspecified"))
      (node (ref "U19") (pin "8") (pinfunction "GND_8") (pintype "unspecified"))
      (node (ref "U2") (pin "1") (pinfunction "GND_1") (pintype "unspecified"))
      (node (ref "U3") (pin "8") (pinfunction "GND_8") (pintype "unspecified"))
      (node (ref "U5") (pin "8") (pinfunction "GND_8") (pintype "unspecified"))
      (node (ref "UP-NEXTPAGE") (pin "2") (pinfunction "2_2") (pintype "input"))
      (node (ref "V") (pin "2") (pinfunction "2_2") (pintype "input"))
      (node (ref "W") (pin "2") (pinfunction "2_2") (pintype "input"))
      (node (ref "X") (pin "2") (pinfunction "2_2") (pintype "input"))
      (node (ref "Y") (pin "2") (pinfunction "2_2") (pintype "input"))
      (node (ref "Z") (pin "2") (pinfunction "2_2") (pintype "input"))
    )
    (net (code "21") (name "IS_CLOCK") (class "Default")
      (node (ref "U1") (pin "2") (pinfunction "A1_2") (pintype "unspecified"))
      (node (ref "U18") (pin "2") (pinfunction "CLK_2") (pintype "unspecified"))
      (node (ref "U19") (pin "2") (pinfunction "CLK_2") (pintype "unspecified"))
    )
    (net (code "22") (name "IS_DATA") (class "Default")
      (node (ref "U1") (pin "1") (pinfunction "A0_1") (pintype "unspecified"))
      (node (ref "U18") (pin "9") (pinfunction "QH_9") (pintype "unspecified"))
    )
    (net (code "23") (name "IS_LATCH") (class "Default")
      (node (ref "U1") (pin "3") (pinfunction "A2_3") (pintype "unspecified"))
      (node (ref "U18") (pin "1") (pinfunction "SH/LD#_1") (pintype "unspecified"))
      (node (ref "U19") (pin "1") (pinfunction "SH/LD#_1") (pintype "unspecified"))
    )
    (net (code "24") (name "L") (class "Default")
      (node (ref "L") (pin "1") (pinfunction "1_1") (pintype "input"))
      (node (ref "U1") (pin "19") (pinfunction "D34_19") (pintype "unspecified"))
    )
    (net (code "25") (name "L1") (class "Default")
      (node (ref "LS1") (pin "1") (pinfunction "1_1") (pintype "input"))
      (node (ref "RN3") (pin "1") (pinfunction "1_1") (pintype "input"))
      (node (ref "U19") (pin "3") (pinfunction "E_3") (pintype "unspecified"))
    )
    (net (code "26") (name "L2") (class "Default")
      (node (ref "LS2") (pin "1") (pinfunction "1_1") (pintype "input"))
      (node (ref "RN3") (pin "2") (pinfunction "2_2") (pintype "input"))
      (node (ref "U19") (pin "4") (pinfunction "F_4") (pintype "unspecified"))
    )
    (net (code "27") (name "L3") (class "Default")
      (node (ref "LS3") (pin "1") (pinfunction "1_1") (pintype "input"))
      (node (ref "RN3") (pin "3") (pinfunction "3_3") (pintype "input"))
      (node (ref "U19") (pin "5") (pinfunction "G_5") (pintype "unspecified"))
    )
    (net (code "28") (name "L4") (class "Default")
      (node (ref "LS4") (pin "1") (pinfunction "1_1") (pintype "input"))
      (node (ref "RN3") (pin "4") (pinfunction "4_4") (pintype "input"))
      (node (ref "U19") (pin "6") (pinfunction "H_6") (pintype "unspecified"))
    )
    (net (code "29") (name "L5") (class "Default")
      (node (ref "LS5") (pin "1") (pinfunction "1_1") (pintype "input"))
      (node (ref "RN4") (pin "8") (pinfunction "8_8") (pintype "input"))
      (node (ref "U19") (pin "14") (pinfunction "D_14") (pintype "unspecified"))
    )
    (net (code "30") (name "L6") (class "Default")
      (node (ref "LS6") (pin "1") (pinfunction "1_1") (pintype "input"))
      (node (ref "RN4") (pin "7") (pinfunction "7_7") (pintype "input"))
      (node (ref "U19") (pin "13") (pinfunction "C_13") (pintype "unspecified"))
    )
    (net (code "31") (name "LEDDRV_CLK") (class "Default")
      (node (ref "U1") (pin "5") (pinfunction "A4_5") (pintype "unspecified"))
      (node (ref "U2") (pin "3") (pinfunction "CLK_3") (pintype "unspecified"))
      (node (ref "U3") (pin "11") (pinfunction "SHIFT_CLOCK_11") (pintype "unspecified"))
      (node (ref "U5") (pin "11") (pinfunction "SHIFT_CLOCK_11") (pintype "unspecified"))
    )
    (net (code "32") (name "LEDDRV_DATA") (class "Default")
      (node (ref "U1") (pin "4") (pinfunction "A3_4") (pintype "unspecified"))
      (node (ref "U2") (pin "2") (pinfunction "SDI_2") (pintype "unspecified"))
      (node (ref "U5") (pin "14") (pinfunction "A_14") (pintype "unspecified"))
    )
    (net (code "33") (name "LEDDRV_LATCH") (class "Default")
      (node (ref "U1") (pin "6") (pinfunction "A5_6") (pintype "unspecified"))
      (node (ref "U2") (pin "4") (pinfunction "LE_4") (pintype "unspecified"))
      (node (ref "U3") (pin "12") (pinfunction "LATCH_CLOCK_12") (pintype "unspecified"))
      (node (ref "U5") (pin "12") (pinfunction "LATCH_CLOCK_12") (pintype "unspecified"))
    )
    (net (code "34") (name "Left") (class "Default")
      (node (ref "LEFT-PREVPAGE") (pin "1") (pinfunction "1_1") (pintype "input"))
      (node (ref "U1") (pin "74") (pinfunction "D2_74") (pintype "unspecified"))
    )
    (net (code "35") (name "Net-(LED1-Pad1)") (class "Default")
      (node (ref "LED1") (pin "1") (pinfunction "1_1") (pintype "unspecified"))
      (node (ref "LED3") (pin "2") (pinfunction "2_2") (pintype "unspecified"))
    )
    (net (code "36") (name "Net-(LED1-Pad2)") (class "Default")
      (node (ref "LED1") (pin "2") (pinfunction "2_2") (pintype "unspecified"))
      (node (ref "LED2") (pin "1") (pinfunction "1_1") (pintype "unspecified"))
    )
    (net (code "37") (name "Net-(LED3-Pad1)") (class "Default")
      (node (ref "LED3") (pin "1") (pinfunction "1_1") (pintype "unspecified"))
      (node (ref "R16") (pin "1") (pinfunction "1_1") (pintype "input"))
    )
    (net (code "38") (name "Net-(LED4-Pad1)") (class "Default")
      (node (ref "LED4") (pin "1") (pinfunction "1_1") (pintype "unspecified"))
      (node (ref "R15") (pin "1") (pinfunction "1_1") (pintype "input"))
    )
    (net (code "39") (name "Net-(LED4-Pad2)") (class "Default")
      (node (ref "LED4") (pin "2") (pinfunction "2_2") (pintype "unspecified"))
      (node (ref "LED5") (pin "1") (pinfunction "1_1") (pintype "unspecified"))
    )
    (net (code "40") (name "Net-(LED5-Pad2)") (class "Default")
      (node (ref "LED5") (pin "2") (pinfunction "2_2") (pintype "unspecified"))
      (node (ref "LED6") (pin "1") (pinfunction "1_1") (pintype "unspecified"))
    )
    (net (code "41") (name "Net-(LED7-Pad1)") (class "Default")
      (node (ref "LED7") (pin "1") (pinfunction "1_1") (pintype "unspecified"))
      (node (ref "R14") (pin "1") (pinfunction "1_1") (pintype "input"))
    )
    (net (code "42") (name "Net-(LED7-Pad2)") (class "Default")
      (node (ref "LED7") (pin "2") (pinfunction "2_2") (pintype "unspecified"))
      (node (ref "LED8") (pin "1") (pinfunction "1_1") (pintype "unspecified"))
    )
    (net (code "43") (name "Net-(LED8-Pad2)") (class "Default")
      (node (ref "LED8") (pin "2") (pinfunction "2_2") (pintype "unspecified"))
      (node (ref "LED9") (pin "1") (pinfunction "1_1") (pintype "unspecified"))
    )
    (net (code "44") (name "Net-(LED10-Pad1)") (class "Default")
      (node (ref "LED10") (pin "1") (pinfunction "1_1") (pintype "unspecified"))
      (node (ref "R13") (pin "1") (pinfunction "1_1") (pintype "input"))
    )
    (net (code "45") (name "Net-(LED10-Pad2)") (class "Default")
      (node (ref "LED10") (pin "2") (pinfunction "2_2") (pintype "unspecified"))
      (node (ref "LED11") (pin "1") (pinfunction "1_1") (pintype "unspecified"))
    )
    (net (code "46") (name "Net-(LED11-Pad2)") (class "Default")
      (node (ref "LED11") (pin "2") (pinfunction "2_2") (pintype "unspecified"))
      (node (ref "LED12") (pin "1") (pinfunction "1_1") (pintype "unspecified"))
    )
    (net (code "47") (name "Net-(LED13-Pad1)") (class "Default")
      (node (ref "LED13") (pin "1") (pinfunction "1_1") (pintype "unspecified"))
      (node (ref "R12") (pin "1") (pinfunction "1_1") (pintype "input"))
    )
    (net (code "48") (name "Net-(LED13-Pad2)") (class "Default")
      (node (ref "LED13") (pin "2") (pinfunction "2_2") (pintype "unspecified"))
      (node (ref "LED14") (pin "1") (pinfunction "1_1") (pintype "unspecified"))
    )
    (net (code "49") (name "Net-(LED14-Pad2)") (class "Default")
      (node (ref "LED14") (pin "2") (pinfunction "2_2") (pintype "unspecified"))
      (node (ref "LED15") (pin "1") (pinfunction "1_1") (pintype "unspecified"))
    )
    (net (code "50") (name "Net-(LED16-Pad1)") (class "Default")
      (node (ref "LED16") (pin "1") (pinfunction "1_1") (pintype "unspecified"))
      (node (ref "R11") (pin "1") (pinfunction "1_1") (pintype "input"))
    )
    (net (code "51") (name "Net-(LED16-Pad2)") (class "Default")
      (node (ref "LED16") (pin "2") (pinfunction "2_2") (pintype "unspecified"))
      (node (ref "LED17") (pin "1") (pinfunction "1_1") (pintype "unspecified"))
    )
    (net (code "52") (name "Net-(LED17-Pad2)") (class "Default")
      (node (ref "LED17") (pin "2") (pinfunction "2_2") (pintype "unspecified"))
      (node (ref "LED18") (pin "1") (pinfunction "1_1") (pintype "unspecified"))
    )
    (net (code "53") (name "Net-(LED19-Pad1)") (class "Default")
      (node (ref "LED19") (pin "1") (pinfunction "1_1") (pintype "unspecified"))
      (node (ref "R10") (pin "1") (pinfunction "1_1") (pintype "input"))
    )
    (net (code "54") (name "Net-(LED19-Pad2)") (class "Default")
      (node (ref "LED19") (pin "2") (pinfunction "2_2") (pintype "unspecified"))
      (node (ref "LED20") (pin "1") (pinfunction "1_1") (pintype "unspecified"))
    )
    (net (code "55") (name "Net-(LED20-Pad2)") (class "Default")
      (node (ref "LED20") (pin "2") (pinfunction "2_2") (pintype "unspecified"))
      (node (ref "LED21") (pin "1") (pinfunction "1_1") (pintype "unspecified"))
    )
    (net (code "56") (name "Net-(LED22-Pad1)") (class "Default")
      (node (ref "LED22") (pin "1") (pinfunction "1_1") (pintype "unspecified"))
      (node (ref "LED23") (pin "2") (pinfunction "2_2") (pintype "unspecified"))
    )
    (net (code "57") (name "Net-(LED23-Pad1)") (class "Default")
      (node (ref "LED23") (pin "1") (pinfunction "1_1") (pintype "unspecified"))
      (node (ref "LED24") (pin "2") (pinfunction "2_2") (pintype "unspecified"))
    )
    (net (code "58") (name "Net-(LED24-Pad1)") (class "Default")
      (node (ref "LED24") (pin "1") (pinfunction "1_1") (pintype "unspecified"))
      (node (ref "R9") (pin "1") (pinfunction "1_1") (pintype "input"))
    )
    (net (code "59") (name "Net-(LED25-Pad1)") (class "Default")
      (node (ref "LED25") (pin "1") (pinfunction "1_1") (pintype "unspecified"))
      (node (ref "LED26") (pin "2") (pinfunction "2_2") (pintype "unspecified"))
    )
    (net (code "60") (name "Net-(LED26-Pad1)") (class "Default")
      (node (ref "LED26") (pin "1") (pinfunction "1_1") (pintype "unspecified"))
      (node (ref "LED27") (pin "2") (pinfunction "2_2") (pintype "unspecified"))
    )
    (net (code "61") (name "Net-(LED27-Pad1)") (class "Default")
      (node (ref "LED27") (pin "1") (pinfunction "1_1") (pintype "unspecified"))
      (node (ref "R3") (pin "1") (pinfunction "1_1") (pintype "input"))
    )
    (net (code "62") (name "Net-(LED28-Pad1)") (class "Default")
      (node (ref "LED28") (pin "1") (pinfunction "1_1") (pintype "unspecified"))
      (node (ref "LED29") (pin "2") (pinfunction "2_2") (pintype "unspecified"))
    )
    (net (code "63") (name "Net-(LED29-Pad1)") (class "Default")
      (node (ref "LED29") (pin "1") (pinfunction "1_1") (pintype "unspecified"))
      (node (ref "LED30") (pin "2") (pinfunction "2_2") (pintype "unspecified"))
    )
    (net (code "64") (name "Net-(LED30-Pad1)") (class "Default")
      (node (ref "LED30") (pin "1") (pinfunction "1_1") (pintype "unspecified"))
      (node (ref "R2") (pin "1") (pinfunction "1_1") (pintype "input"))
    )
    (net (code "65") (name "Net-(LED31-Pad1)") (class "Default")
      (node (ref "LED31") (pin "1") (pinfunction "1_1") (pintype "unspecified"))
      (node (ref "R1") (pin "1") (pinfunction "1_1") (pintype "input"))
    )
    (net (code "66") (name "Net-(LED31-Pad2)") (class "Default")
      (node (ref "LED31") (pin "2") (pinfunction "2_2") (pintype "unspecified"))
      (node (ref "LED32") (pin "1") (pinfunction "1_1") (pintype "unspecified"))
    )
    (net (code "67") (name "Net-(LED32-Pad2)") (class "Default")
      (node (ref "LED32") (pin "2") (pinfunction "2_2") (pintype "unspecified"))
      (node (ref "LED33") (pin "1") (pinfunction "1_1") (pintype "unspecified"))
    )
    (net (code "68") (name "Net-(Q2-G)") (class "Default")
      (node (ref "Q2") (pin "1") (pinfunction "G_1") (pintype "unspecified"))
      (node (ref "R17") (pin "2") (pinfunction "2_2") (pintype "input"))
      (node (ref "R7") (pin "2") (pinfunction "2_2") (pintype "input"))
    )
    (net (code "69") (name "Net-(U2-REXT)") (class "Default")
      (node (ref "R8") (pin "1") (pinfunction "1_1") (pintype "input"))
      (node (ref "U2") (pin "23") (pinfunction "REXT_23") (pintype "unspecified"))
    )
    (net (code "70") (name "Net-(U3-A)") (class "Default")
      (node (ref "U3") (pin "14") (pinfunction "A_14") (pintype "unspecified"))
      (node (ref "U5") (pin "9") (pinfunction "SQH_9") (pintype "unspecified"))
    )
    (net (code "71") (name "Net-(U18-SER)") (class "Default")
      (node (ref "U18") (pin "10") (pinfunction "SER_10") (pintype "unspecified"))
      (node (ref "U19") (pin "9") (pinfunction "QH_9") (pintype "unspecified"))
    )
    (net (code "72") (name "R1") (class "Default")
      (node (ref "RS1") (pin "1") (pinfunction "1_1") (pintype "input"))
      (node (ref "U1") (pin "45") (pinfunction "D31_45") (pintype "unspecified"))
    )
    (net (code "73") (name "R2") (class "Default")
      (node (ref "RS2") (pin "1") (pinfunction "1_1") (pintype "input"))
      (node (ref "U1") (pin "46") (pinfunction "D30_46") (pintype "unspecified"))
    )
    (net (code "74") (name "R3") (class "Default")
      (node (ref "RS3") (pin "1") (pinfunction "1_1") (pintype "input"))
      (node (ref "U1") (pin "47") (pinfunction "D29_47") (pintype "unspecified"))
    )
    (net (code "75") (name "R4") (class "Default")
      (node (ref "RS4") (pin "1") (pinfunction "1_1") (pintype "input"))
      (node (ref "U1") (pin "48") (pinfunction "D28_48") (pintype "unspecified"))
    )
    (net (code "76") (name "R5") (class "Default")
      (node (ref "RS5") (pin "1") (pinfunction "1_1") (pintype "input"))
      (node (ref "U1") (pin "49") (pinfunction "D27_49") (pintype "unspecified"))
    )
    (net (code "77") (name "R6") (class "Default")
      (node (ref "RS6") (pin "1") (pinfunction "1_1") (pintype "input"))
      (node (ref "U1") (pin "50") (pinfunction "D26_50") (pintype "unspecified"))
    )
    (net (code "78") (name "Right") (class "Default")
      (node (ref "RIGHT-NULL") (pin "1") (pinfunction "1_1") (pintype "input"))
      (node (ref "U1") (pin "72") (pinfunction "D4_72") (pintype "unspecified"))
    )
    (net (code "79") (name "a") (class "Default")
      (node (ref "A") (pin "1") (pinfunction "1_1") (pintype "input"))
      (node (ref "U1") (pin "65") (pinfunction "D11_65") (pintype "unspecified"))
    )
    (net (code "80") (name "atccomm") (class "Default")
      (node (ref "ATCCOMM-PROG") (pin "1") (pinfunction "1_1") (pintype "input"))
      (node (ref "U1") (pin "58") (pinfunction "D18_58") (pintype "unspecified"))
    )
    (net (code "81") (name "b") (class "Default")
      (node (ref "B") (pin "1") (pinfunction "1_1") (pintype "input"))
      (node (ref "U1") (pin "62") (pinfunction "D14_62") (pintype "unspecified"))
    )
    (net (code "82") (name "blank1") (class "Default")
      (node (ref "BLANK1-FIX") (pin "1") (pinfunction "1_1") (pintype "input"))
      (node (ref "U1") (pin "36") (pinfunction "D51_36") (pintype "unspecified"))
    )
    (net (code "83") (name "blank2") (class "Default")
      (node (ref "BLANK2-NULL") (pin "1") (pinfunction "1_1") (pintype "input"))
      (node (ref "U1") (pin "53") (pinfunction "D23_53") (pintype "unspecified"))
    )
    (net (code "84") (name "brt") (class "Default")
      (node (ref "BRT") (pin "1") (pinfunction "1_1") (pintype "input"))
      (node (ref "U1") (pin "38") (pinfunction "D53_38") (pintype "unspecified"))
    )
    (net (code "85") (name "c") (class "Default")
      (node (ref "C") (pin "1") (pinfunction "1_1") (pintype "input"))
      (node (ref "U1") (pin "61") (pinfunction "D15_61") (pintype "unspecified"))
    )
    (net (code "86") (name "clr") (class "Default")
      (node (ref "CLR") (pin "1") (pinfunction "1_1") (pintype "input"))
      (node (ref "RN5") (pin "8") (pinfunction "8_8") (pintype "input"))
      (node (ref "U18") (pin "14") (pinfunction "D_14") (pintype "unspecified"))
    )
    (net (code "87") (name "d") (class "Default")
      (node (ref "D") (pin "1") (pinfunction "1_1") (pintype "input"))
      (node (ref "U1") (pin "60") (pinfunction "D16_60") (pintype "unspecified"))
    )
    (net (code "88") (name "data") (class "Default")
      (node (ref "DATA-DES") (pin "1") (pinfunction "1_1") (pintype "input"))
      (node (ref "U1") (pin "52") (pinfunction "D24_52") (pintype "unspecified"))
    )
    (net (code "89") (name "dim") (class "Default")
      (node (ref "DIM") (pin "1") (pinfunction "1_1") (pintype "input"))
      (node (ref "U1") (pin "37") (pinfunction "D52_37") (pintype "unspecified"))
    )
    (net (code "90") (name "dot") (class "Default")
      (node (ref "DOT") (pin "1") (pinfunction "1_1") (pintype "input"))
      (node (ref "U1") (pin "12") (pinfunction "A11_12") (pintype "unspecified"))
    )
    (net (code "91") (name "e") (class "Default")
      (node (ref "E") (pin "1") (pinfunction "1_1") (pintype "input"))
      (node (ref "U1") (pin "59") (pinfunction "D17_59") (pintype "unspecified"))
    )
    (net (code "92") (name "exec") (class "Default")
      (node (ref "EXEC") (pin "1") (pinfunction "K_1") (pintype "unspecified"))
      (node (ref "U2") (pin "15") (pinfunction "OUT10_15") (pintype "unspecified"))
      (node (ref "U3") (pin "1") (pinfunction "QB_1") (pintype "unspecified"))
    )
    (net (code "93") (name "f") (class "Default")
      (node (ref "F") (pin "1") (pinfunction "1_1") (pintype "input"))
      (node (ref "U1") (pin "15") (pinfunction "A14_15") (pintype "unspecified"))
    )
    (net (code "94") (name "fuelpred") (class "Default")
      (node (ref "FUELPRED-DEPARR") (pin "1") (pinfunction "1_1") (pintype "input"))
      (node (ref "U1") (pin "54") (pinfunction "D22_54") (pintype "unspecified"))
    )
    (net (code "95") (name "g") (class "Default")
      (node (ref "G") (pin "1") (pinfunction "1_1") (pintype "input"))
      (node (ref "U1") (pin "16") (pinfunction "A15_16") (pintype "unspecified"))
    )
    (net (code "96") (name "h") (class "Default")
      (node (ref "H") (pin "1") (pinfunction "1_1") (pintype "input"))
      (node (ref "U1") (pin "17") (pinfunction "D32_17") (pintype "unspecified"))
    )
    (net (code "97") (name "i") (class "Default")
      (node (ref "I") (pin "1") (pinfunction "1_1") (pintype "input"))
      (node (ref "U1") (pin "34") (pinfunction "D49_34") (pintype "unspecified"))
    )
    (net (code "98") (name "indicator1") (class "Default")
      (node (ref "INDICATOR1") (pin "1") (pinfunction "K_1") (pintype "unspecified"))
      (node (ref "U2") (pin "5") (pinfunction "OUT0_5") (pintype "unspecified"))
      (node (ref "U5") (pin "15") (pinfunction "QA_15") (pintype "unspecified"))
    )
    (net (code "99") (name "indicator2") (class "Default")
      (node (ref "INDICATOR2") (pin "1") (pinfunction "K_1") (pintype "unspecified"))
      (node (ref "U2") (pin "6") (pinfunction "OUT1_6") (pintype "unspecified"))
      (node (ref "U5") (pin "6") (pinfunction "QG_6") (pintype "unspecified"))
    )
    (net (code "100") (name "indicator3") (class "Default")
      (node (ref "INDICATOR3") (pin "1") (pinfunction "K_1") (pintype "unspecified"))
      (node (ref "U2") (pin "7") (pinfunction "OUT2_7") (pintype "unspecified"))
      (node (ref "U5") (pin "5") (pinfunction "QF_5") (pintype "unspecified"))
    )
    (net (code "101") (name "indicator4") (class "Default")
      (node (ref "INDICATOR4") (pin "1") (pinfunction "K_1") (pintype "unspecified"))
      (node (ref "U2") (pin "8") (pinfunction "OUT3_8") (pintype "unspecified"))
      (node (ref "U5") (pin "4") (pinfunction "QE_4") (pintype "unspecified"))
    )
    (net (code "102") (name "indicator5") (class "Default")
      (node (ref "INDICATOR5") (pin "1") (pinfunction "K_1") (pintype "unspecified"))
      (node (ref "U2") (pin "9") (pinfunction "OUT4_9") (pintype "unspecified"))
      (node (ref "U5") (pin "3") (pinfunction "QD_3") (pintype "unspecified"))
    )
    (net (code "103") (name "indicator6") (class "Default")
      (node (ref "INDICATOR6") (pin "2") (pinfunction "K_2") (pintype "unspecified"))
      (node (ref "U2") (pin "10") (pinfunction "OUT5_10") (pintype "unspecified"))
      (node (ref "U5") (pin "2") (pinfunction "QC_2") (pintype "unspecified"))
    )
    (net (code "104") (name "indicator6a") (class "Default")
      (node (ref "INDICATOR6A") (pin "2") (pinfunction "K_2") (pintype "unspecified"))
      (node (ref "U2") (pin "11") (pinfunction "OUT6_11") (pintype "unspecified"))
      (node (ref "U5") (pin "1") (pinfunction "QB_1") (pintype "unspecified"))
    )
    (net (code "105") (name "indicator7") (class "Default")
      (node (ref "INDICATOR7") (pin "1") (pinfunction "K_1") (pintype "unspecified"))
      (node (ref "U2") (pin "12") (pinfunction "OUT7_12") (pintype "unspecified"))
      (node (ref "U3") (pin "4") (pinfunction "QE_4") (pintype "unspecified"))
    )
    (net (code "106") (name "indicator8") (class "Default")
      (node (ref "INDICATOR8") (pin "1") (pinfunction "K_1") (pintype "unspecified"))
      (node (ref "U2") (pin "13") (pinfunction "OUT8_13") (pintype "unspecified"))
      (node (ref "U3") (pin "3") (pinfunction "QD_3") (pintype "unspecified"))
    )
    (net (code "107") (name "indicator9") (class "Default")
      (node (ref "INDICATOR9") (pin "1") (pinfunction "K_1") (pintype "unspecified"))
      (node (ref "U2") (pin "14") (pinfunction "OUT9_14") (pintype "unspecified"))
      (node (ref "U3") (pin "2") (pinfunction "QC_2") (pintype "unspecified"))
    )
    (net (code "108") (name "init") (class "Default")
      (node (ref "INIT-CRZ") (pin "1") (pinfunction "1_1") (pintype "input"))
      (node (ref "U1") (pin "35") (pinfunction "D50_35") (pintype "unspecified"))
    )
    (net (code "109") (name "j") (class "Default")
      (node (ref "J") (pin "1") (pinfunction "1_1") (pintype "input"))
      (node (ref "U1") (pin "33") (pinfunction "D48_33") (pintype "unspecified"))
    )
    (net (code "110") (name "k") (class "Default")
      (node (ref "K") (pin "1") (pinfunction "1_1") (pintype "input"))
      (node (ref "U1") (pin "18") (pinfunction "D33_18") (pintype "unspecified"))
    )
    (net (code "111") (name "m") (class "Default")
      (node (ref "M") (pin "1") (pinfunction "1_1") (pintype "input"))
      (node (ref "U1") (pin "20") (pinfunction "D35_20") (pintype "unspecified"))
    )
    (net (code "112") (name "mcdumenu") (class "Default")
      (node (ref "MCDUMENU-EXEC") (pin "1") (pinfunction "1_1") (pintype "input"))
      (node (ref "U1") (pin "51") (pinfunction "D25_51") (pintype "unspecified"))
    )
    (net (code "113") (name "n") (class "Default")
      (node (ref "N") (pin "1") (pinfunction "1_1") (pintype "input"))
      (node (ref "RN6") (pin "1") (pinfunction "1_1") (pintype "input"))
      (node (ref "U18") (pin "3") (pinfunction "E_3") (pintype "unspecified"))
    )
    (net (code "114") (name "o") (class "Default")
      (node (ref "O") (pin "1") (pinfunction "1_1") (pintype "input"))
      (node (ref "RN6") (pin "2") (pinfunction "2_2") (pintype "input"))
      (node (ref "U18") (pin "4") (pinfunction "F_4") (pintype "unspecified"))
    )
    (net (code "115") (name "ovfy") (class "Default")
      (node (ref "OVFY") (pin "1") (pinfunction "1_1") (pintype "input"))
      (node (ref "RN5") (pin "6") (pinfunction "6_6") (pintype "input"))
      (node (ref "U18") (pin "12") (pinfunction "B_12") (pintype "unspecified"))
    )
    (net (code "116") (name "p") (class "Default")
      (node (ref "P") (pin "1") (pinfunction "1_1") (pintype "input"))
      (node (ref "U1") (pin "22") (pinfunction "D37_22") (pintype "unspecified"))
    )
    (net (code "117") (name "perf") (class "Default")
      (node (ref "PERF-CLB") (pin "1") (pinfunction "1_1") (pintype "input"))
      (node (ref "U1") (pin "55") (pinfunction "D21_55") (pintype "unspecified"))
    )
    (net (code "118") (name "plusminus") (class "Default")
      (node (ref "PLUSMINUS") (pin "1") (pinfunction "1_1") (pintype "input"))
      (node (ref "U1") (pin "14") (pinfunction "A13_14") (pintype "unspecified"))
    )
    (net (code "119") (name "prog") (class "Default")
      (node (ref "PROG-RTE") (pin "1") (pinfunction "1_1") (pintype "input"))
      (node (ref "U1") (pin "57") (pinfunction "D19_57") (pintype "unspecified"))
    )
    (net (code "120") (name "q") (class "Default")
      (node (ref "Q") (pin "1") (pinfunction "1_1") (pintype "input"))
      (node (ref "U1") (pin "23") (pinfunction "D38_23") (pintype "unspecified"))
    )
    (net (code "121") (name "r") (class "Default")
      (node (ref "R") (pin "1") (pinfunction "1_1") (pintype "input"))
      (node (ref "U1") (pin "24") (pinfunction "D39_24") (pintype "unspecified"))
    )
    (net (code "122") (name "radnav") (class "Default")
      (node (ref "RADNAV-LEGS") (pin "1") (pinfunction "1_1") (pintype "input"))
      (node (ref "U1") (pin "56") (pinfunction "D20_56") (pintype "unspecified"))
    )
    (net (code "123") (name "s") (class "Default")
      (node (ref "RN6") (pin "3") (pinfunction "3_3") (pintype "input"))
      (node (ref "S") (pin "1") (pinfunction "1_1") (pintype "input"))
      (node (ref "U18") (pin "5") (pinfunction "G_5") (pintype "unspecified"))
    )
    (net (code "124") (name "secfpln") (class "Default")
      (node (ref "SECFPLN-HOLD") (pin "1") (pinfunction "1_1") (pintype "input"))
      (node (ref "U1") (pin "21") (pinfunction "D36_21") (pintype "unspecified"))
    )
    (net (code "125") (name "sp") (class "Default")
      (node (ref "SP") (pin "1") (pinfunction "1_1") (pintype "input"))
      (node (ref "U1") (pin "32") (pinfunction "D47_32") (pintype "unspecified"))
    )
    (net (code "126") (name "t") (class "Default")
      (node (ref "RN6") (pin "4") (pinfunction "4_4") (pintype "input"))
      (node (ref "T") (pin "1") (pinfunction "1_1") (pintype "input"))
      (node (ref "U18") (pin "6") (pinfunction "H_6") (pintype "unspecified"))
    )
    (net (code "127") (name "u") (class "Default")
      (node (ref "U") (pin "1") (pinfunction "1_1") (pintype "input"))
      (node (ref "U1") (pin "26") (pinfunction "D41_26") (pintype "unspecified"))
    )
    (net (code "128") (name "unconnected-(R4-Pad2)") (class "Default")
      (node (ref "R4") (pin "2") (pinfunction "2_2") (pintype "input"))
    )
    (net (code "129") (name "unconnected-(R5-Pad2)") (class "Default")
      (node (ref "R5") (pin "2") (pinfunction "2_2") (pintype "input"))
    )
    (net (code "130") (name "unconnected-(R6-Pad2)") (class "Default")
      (node (ref "R6") (pin "2") (pinfunction "2_2") (pintype "input"))
    )
    (net (code "131") (name "unconnected-(R18-Pad2)") (class "Default")
      (node (ref "R18") (pin "2") (pinfunction "2_2") (pintype "input"))
    )
    (net (code "132") (name "unconnected-(R19-Pad2)") (class "Default")
      (node (ref "R19") (pin "2") (pinfunction "2_2") (pintype "input"))
    )
    (net (code "133") (name "unconnected-(R20-Pad2)") (class "Default")
      (node (ref "R20") (pin "2") (pinfunction "2_2") (pintype "input"))
    )
    (net (code "134") (name "unconnected-(R21-Pad2)") (class "Default")
      (node (ref "R21") (pin "2") (pinfunction "2_2") (pintype "input"))
    )
    (net (code "135") (name "unconnected-(R22-Pad2)") (class "Default")
      (node (ref "R22") (pin "2") (pinfunction "2_2") (pintype "input"))
    )
    (net (code "136") (name "unconnected-(R23-Pad2)") (class "Default")
      (node (ref "R23") (pin "2") (pinfunction "2_2") (pintype "input"))
    )
    (net (code "137") (name "unconnected-(R24-Pad2)") (class "Default")
      (node (ref "R24") (pin "2") (pinfunction "2_2") (pintype "input"))
    )
    (net (code "138") (name "unconnected-(R25-Pad2)") (class "Default")
      (node (ref "R25") (pin "2") (pinfunction "2_2") (pintype "input"))
    )
    (net (code "139") (name "unconnected-(U1-3.3V-Pad79)") (class "Default")
      (node (ref "U1") (pin "79") (pinfunction "3.3V_79") (pintype "unspecified+no_connect"))
    )
    (net (code "140") (name "unconnected-(U1-3.3V-Pad80)") (class "Default")
      (node (ref "U1") (pin "80") (pinfunction "3.3V_80") (pintype "unspecified+no_connect"))
    )
    (net (code "141") (name "unconnected-(U1-A6-Pad7)") (class "Default")
      (node (ref "U1") (pin "7") (pinfunction "A6_7") (pintype "unspecified+no_connect"))
    )
    (net (code "142") (name "unconnected-(U1-AREF-Pad78)") (class "Default")
      (node (ref "U1") (pin "78") (pinfunction "AREF_78") (pintype "unspecified+no_connect"))
    )
    (net (code "143") (name "unconnected-(U1-D44-Pad29)") (class "Default")
      (node (ref "U1") (pin "29") (pinfunction "D44_29") (pintype "unspecified+no_connect"))
    )
    (net (code "144") (name "unconnected-(U1-MISO-Pad40)") (class "Default")
      (node (ref "U1") (pin "40") (pinfunction "MISO_40") (pintype "unspecified+no_connect"))
    )
    (net (code "145") (name "unconnected-(U1-MOSI-Pad41)") (class "Default")
      (node (ref "U1") (pin "41") (pinfunction "MOSI_41") (pintype "unspecified+no_connect"))
    )
    (net (code "146") (name "unconnected-(U1-RX-Pad76)") (class "Default")
      (node (ref "U1") (pin "76") (pinfunction "RX_76") (pintype "unspecified+no_connect"))
    )
    (net (code "147") (name "unconnected-(U1-Reset-Pad44)") (class "Default")
      (node (ref "U1") (pin "44") (pinfunction "Reset_44") (pintype "unspecified+no_connect"))
    )
    (net (code "148") (name "unconnected-(U1-Reset-Pad77)") (class "Default")
      (node (ref "U1") (pin "77") (pinfunction "Reset_77") (pintype "unspecified+no_connect"))
    )
    (net (code "149") (name "unconnected-(U1-SCK-Pad42)") (class "Default")
      (node (ref "U1") (pin "42") (pinfunction "SCK_42") (pintype "unspecified+no_connect"))
    )
    (net (code "150") (name "unconnected-(U1-TX-Pad75)") (class "Default")
      (node (ref "U1") (pin "75") (pinfunction "TX_75") (pintype "unspecified+no_connect"))
    )
    (net (code "151") (name "unconnected-(U1-VIN-Pad85)") (class "Default")
      (node (ref "U1") (pin "85") (pinfunction "VIN_85") (pintype "unspecified+no_connect"))
    )
    (net (code "152") (name "unconnected-(U1-VIN-Pad86)") (class "Default")
      (node (ref "U1") (pin "86") (pinfunction "VIN_86") (pintype "unspecified+no_connect"))
    )
    (net (code "153") (name "unconnected-(U2-OUT11-Pad16)") (class "Default")
      (node (ref "U2") (pin "16") (pinfunction "OUT11_16") (pintype "unspecified+no_connect"))
    )
    (net (code "154") (name "unconnected-(U2-OUT12-Pad17)") (class "Default")
      (node (ref "U2") (pin "17") (pinfunction "OUT12_17") (pintype "unspecified+no_connect"))
    )
    (net (code "155") (name "unconnected-(U2-OUT13-Pad18)") (class "Default")
      (node (ref "U2") (pin "18") (pinfunction "OUT13_18") (pintype "unspecified+no_connect"))
    )
    (net (code "156") (name "unconnected-(U2-OUT14-Pad19)") (class "Default")
      (node (ref "U2") (pin "19") (pinfunction "OUT14_19") (pintype "unspecified+no_connect"))
    )
    (net (code "157") (name "unconnected-(U2-OUT15-Pad20)") (class "Default")
      (node (ref "U2") (pin "20") (pinfunction "OUT15_20") (pintype "unspecified+no_connect"))
    )
    (net (code "158") (name "unconnected-(U2-SDO-Pad22)") (class "Default")
      (node (ref "U2") (pin "22") (pinfunction "SDO_22") (pintype "unspecified+no_connect"))
    )
    (net (code "159") (name "unconnected-(U3-QA-Pad15)") (class "Default")
      (node (ref "U3") (pin "15") (pinfunction "QA_15") (pintype "unspecified+no_connect"))
    )
    (net (code "160") (name "unconnected-(U3-QF-Pad5)") (class "Default")
      (node (ref "U3") (pin "5") (pinfunction "QF_5") (pintype "unspecified+no_connect"))
    )
    (net (code "161") (name "unconnected-(U3-QG-Pad6)") (class "Default")
      (node (ref "U3") (pin "6") (pinfunction "QG_6") (pintype "unspecified+no_connect"))
    )
    (net (code "162") (name "unconnected-(U3-QH-Pad7)") (class "Default")
      (node (ref "U3") (pin "7") (pinfunction "QH_7") (pintype "unspecified+no_connect"))
    )
    (net (code "163") (name "unconnected-(U3-SQH-Pad9)") (class "Default")
      (node (ref "U3") (pin "9") (pinfunction "SQH_9") (pintype "unspecified+no_connect"))
    )
    (net (code "164") (name "unconnected-(U5-QH-Pad7)") (class "Default")
      (node (ref "U5") (pin "7") (pinfunction "QH_7") (pintype "unspecified+no_connect"))
    )
    (net (code "165") (name "unconnected-(U18-QH#-Pad7)") (class "Default")
      (node (ref "U18") (pin "7") (pinfunction "QH#_7") (pintype "unspecified+no_connect"))
    )
    (net (code "166") (name "unconnected-(U19-QH#-Pad7)") (class "Default")
      (node (ref "U19") (pin "7") (pinfunction "QH#_7") (pintype "unspecified+no_connect"))
    )
    (net (code "167") (name "up") (class "Default")
      (node (ref "U1") (pin "73") (pinfunction "D3_73") (pintype "unspecified"))
      (node (ref "UP-NEXTPAGE") (pin "1") (pinfunction "1_1") (pintype "input"))
    )
    (net (code "168") (name "v") (class "Default")
      (node (ref "U1") (pin "27") (pinfunction "D42_27") (pintype "unspecified"))
      (node (ref "V") (pin "1") (pinfunction "1_1") (pintype "input"))
    )
    (net (code "169") (name "w") (class "Default")
      (node (ref "U1") (pin "28") (pinfunction "D43_28") (pintype "unspecified"))
      (node (ref "W") (pin "1") (pinfunction "1_1") (pintype "input"))
    )
    (net (code "170") (name "x") (class "Default")
      (node (ref "RN5") (pin "5") (pinfunction "5_5") (pintype "input"))
      (node (ref "U18") (pin "11") (pinfunction "A_11") (pintype "unspecified"))
      (node (ref "X") (pin "1") (pinfunction "1_1") (pintype "input"))
    )
    (net (code "171") (name "y") (class "Default")
      (node (ref "RN5") (pin "7") (pinfunction "7_7") (pintype "input"))
      (node (ref "U18") (pin "13") (pinfunction "C_13") (pintype "unspecified"))
      (node (ref "Y") (pin "1") (pinfunction "1_1") (pintype "input"))
    )
    (net (code "172") (name "z") (class "Default")
      (node (ref "U1") (pin "30") (pinfunction "D45_30") (pintype "unspecified"))
      (node (ref "Z") (pin "1") (pinfunction "1_1") (pintype "input"))
    )
    (net (code "173") (name "{slash}") (class "Default")
      (node (ref "/") (pin "1") (pinfunction "1_1") (pintype "input"))
      (node (ref "U1") (pin "31") (pinfunction "D46_31") (pintype "unspecified"))
    )
  )
)
